# TopPrinter-F0_2_1_PCB.net
KiCad netlist of a schematic drawn in Altium Designer
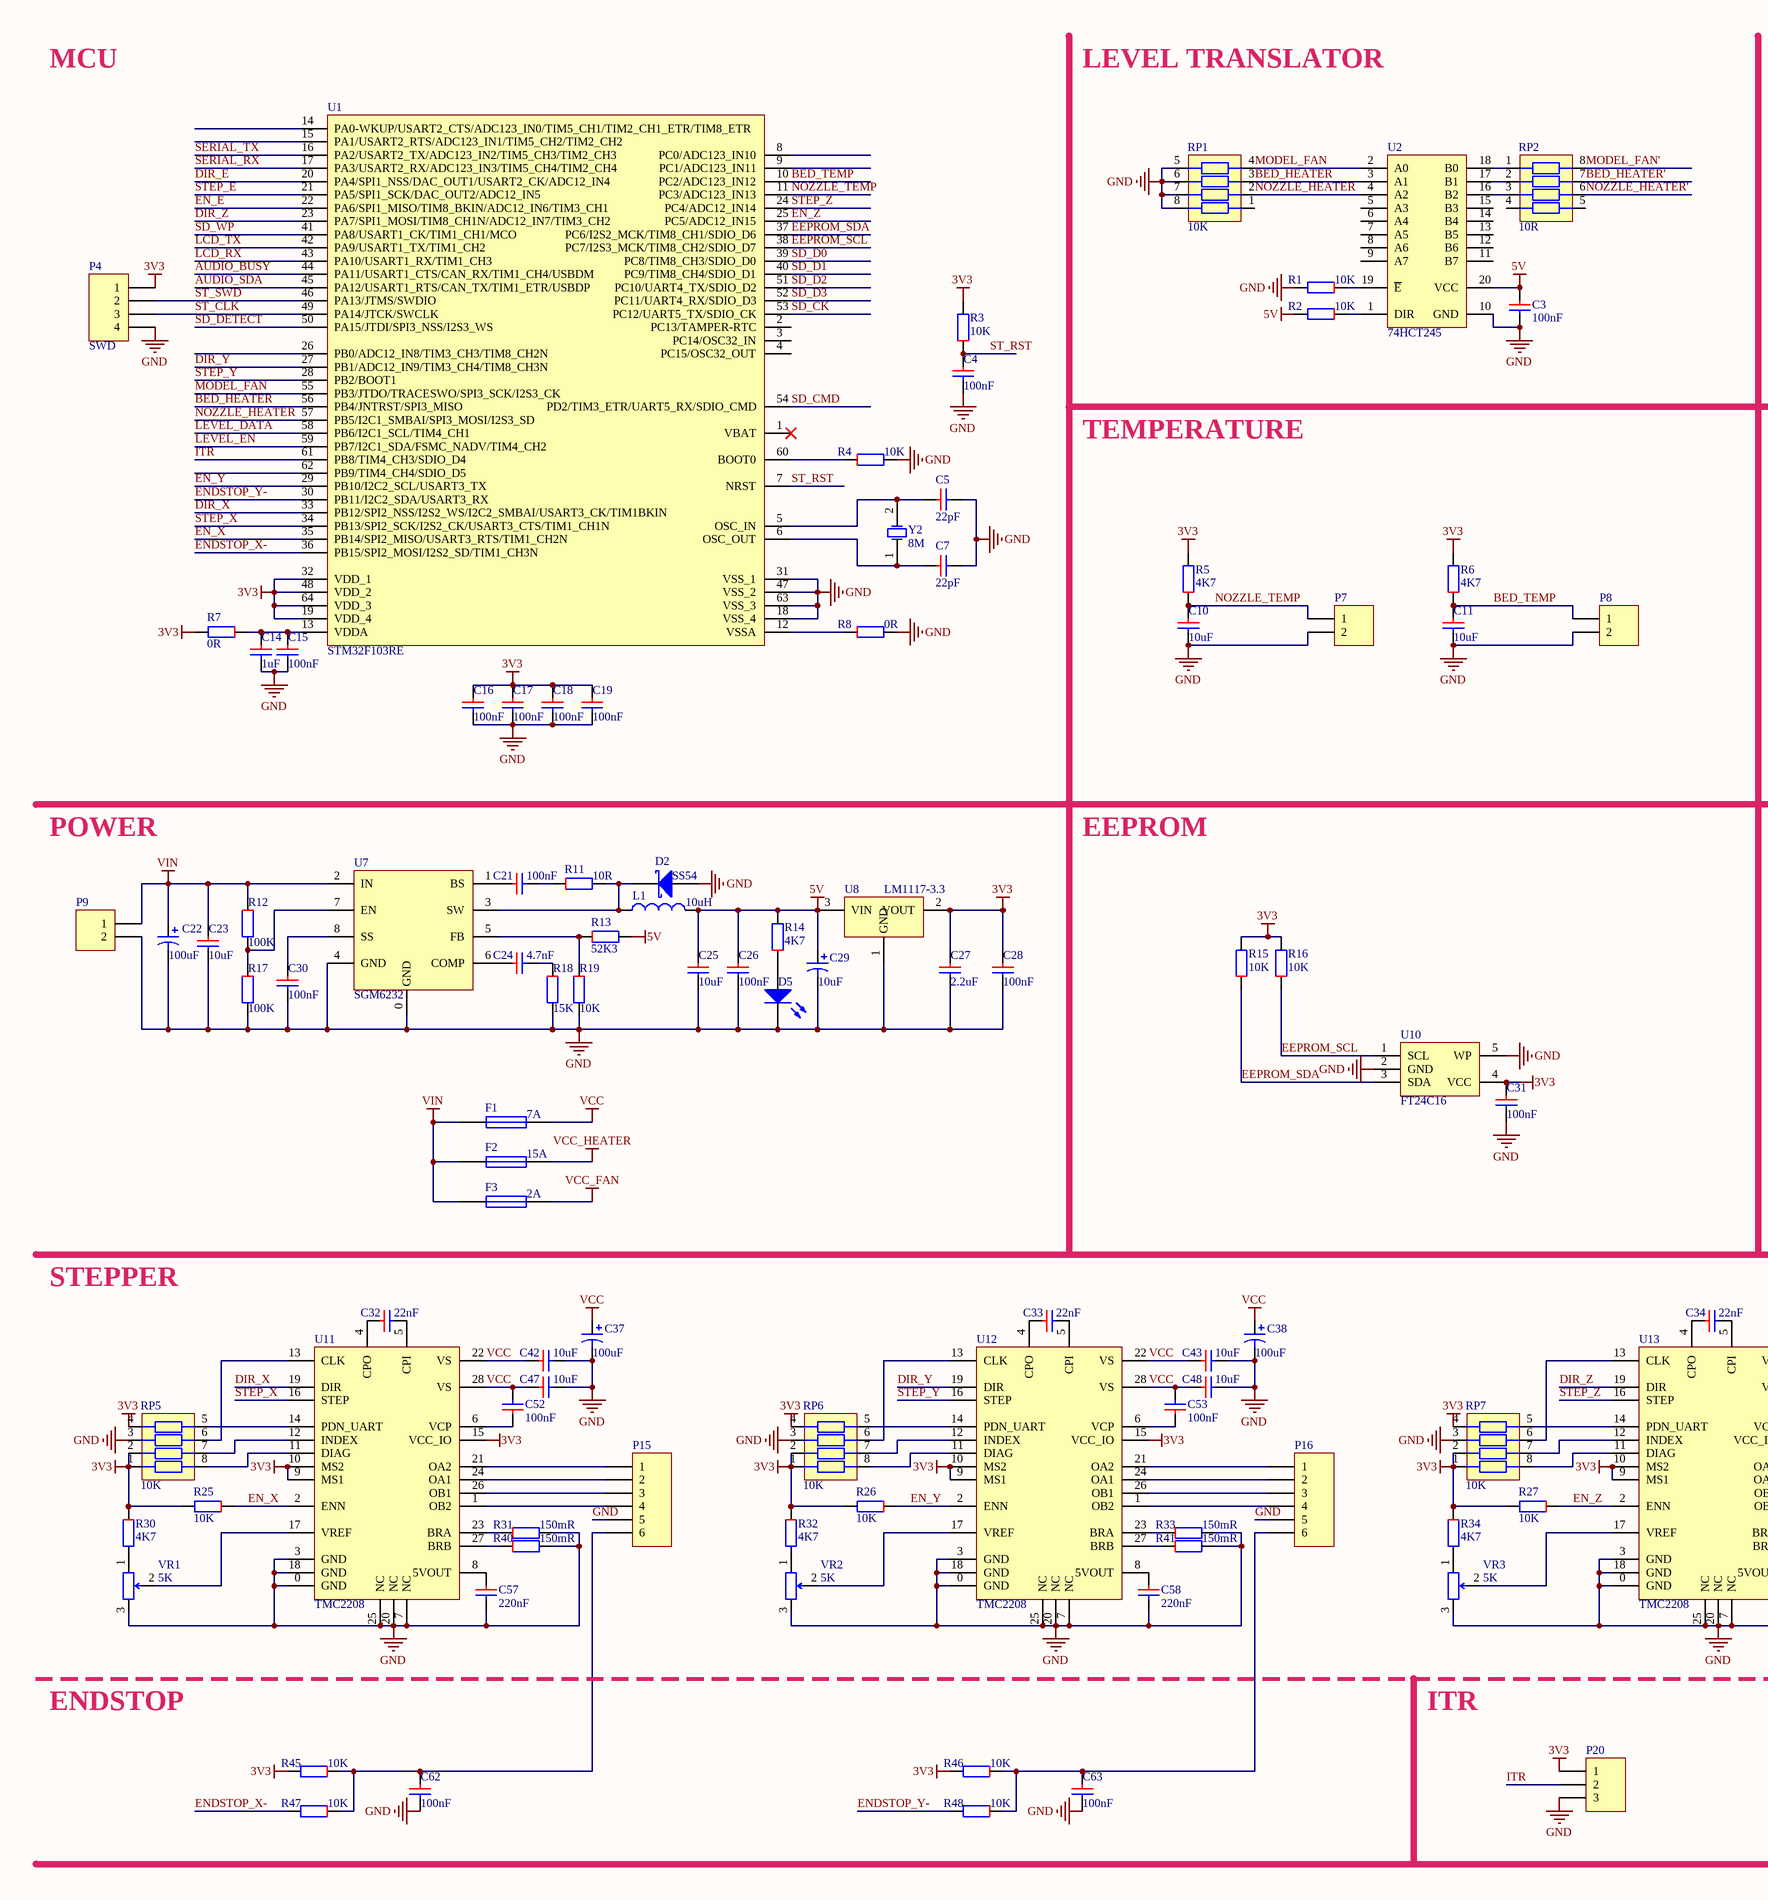
[diagram p0: TopPrinter-F0.2.1_PCB.SchDoc, left]
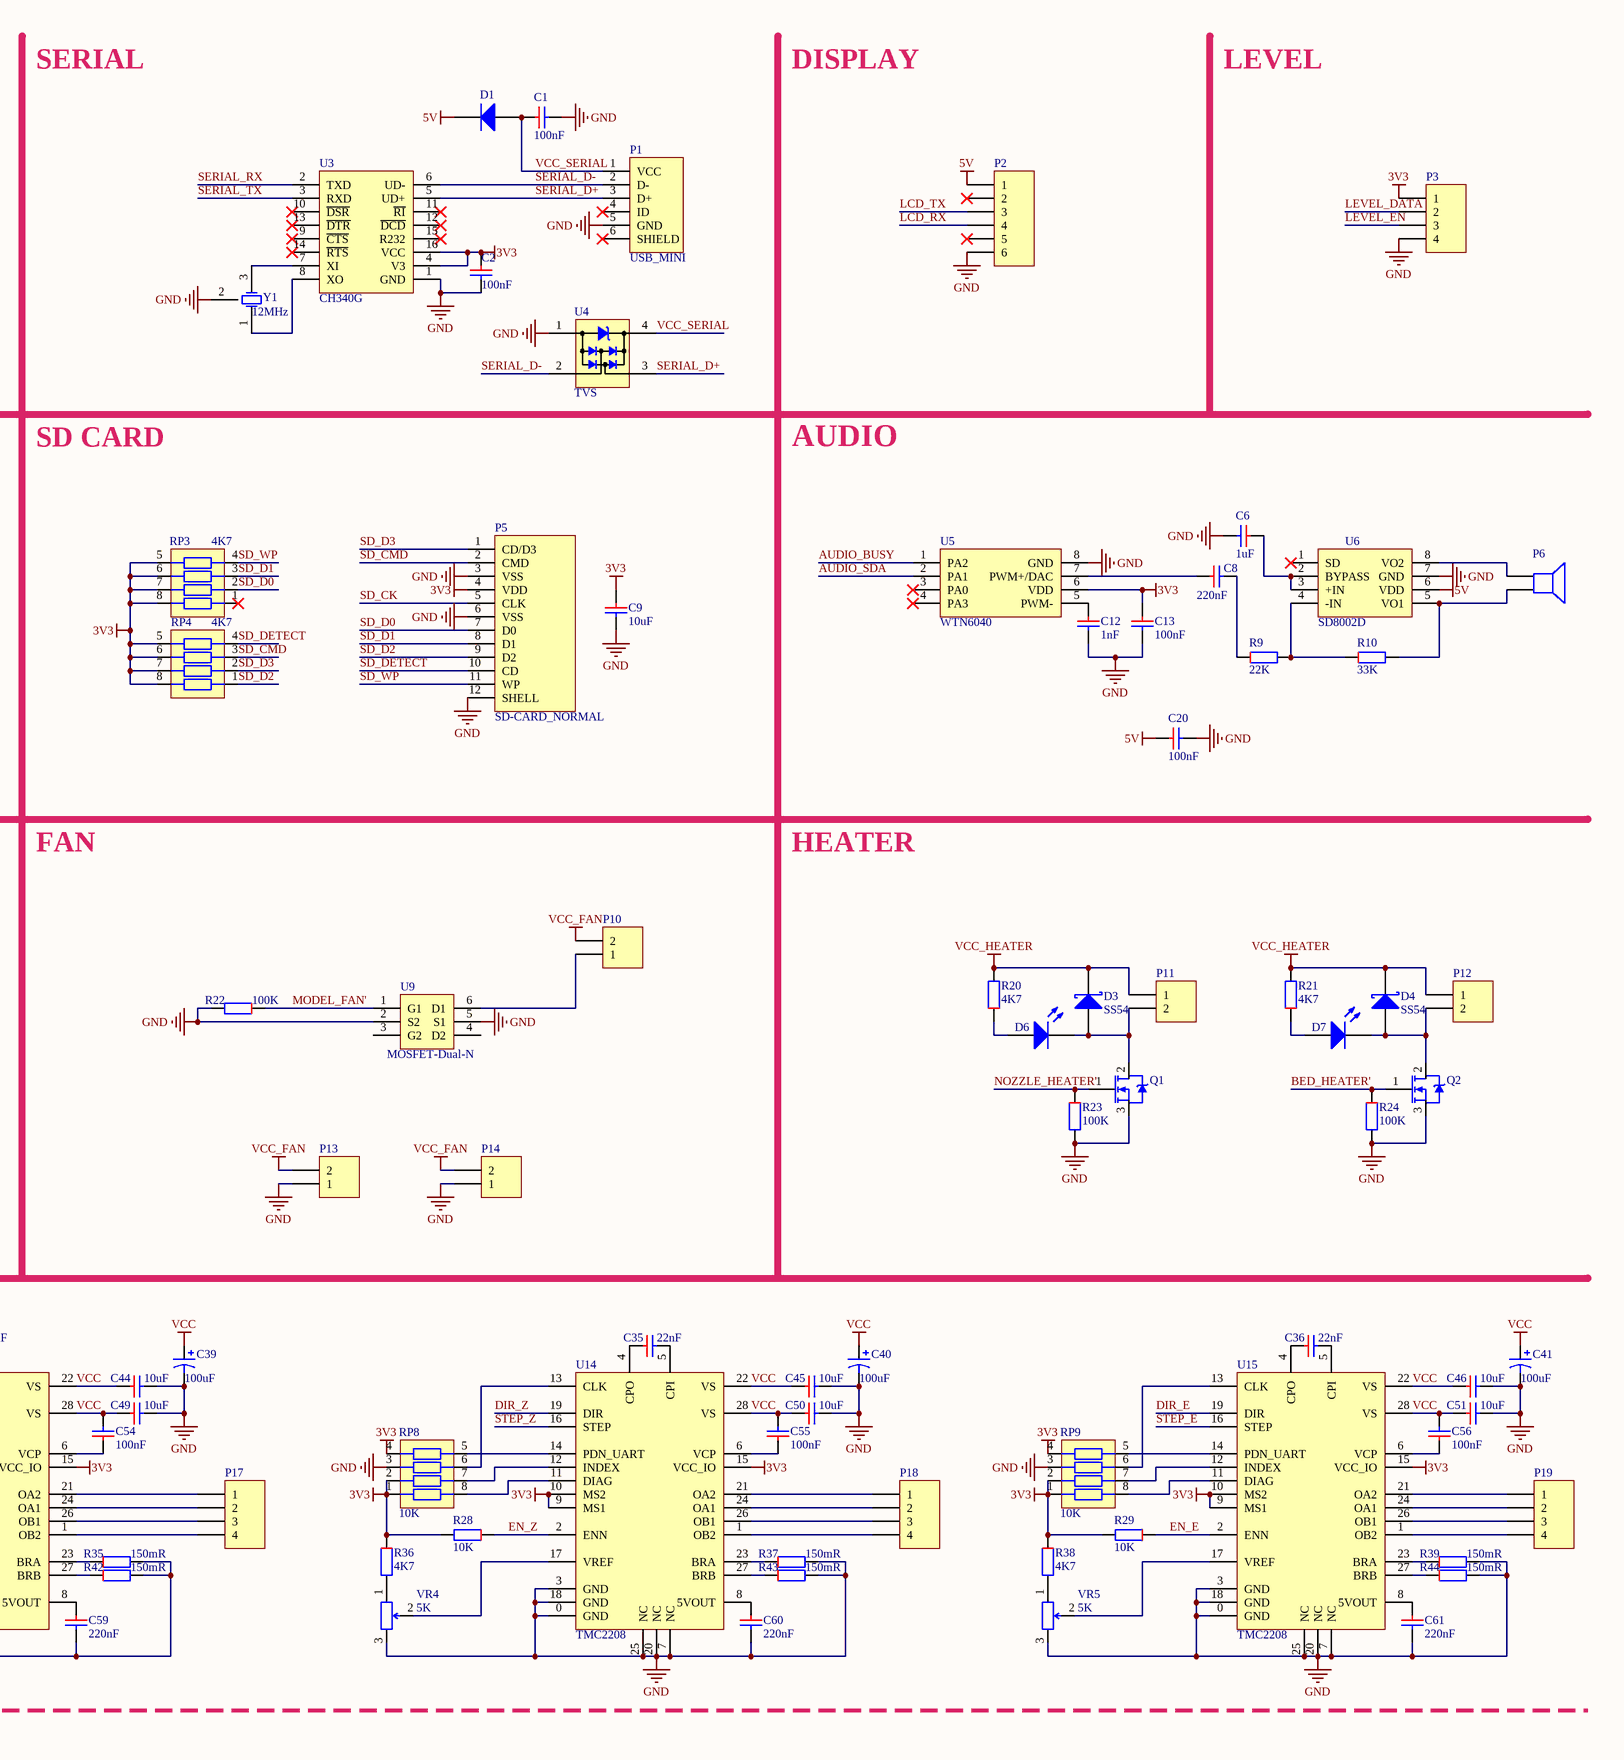
[diagram p1: TopPrinter-F0.2.1_PCB.SchDoc, right]

(export (version "E")
  (design (tool "Eeschema 10.0.6"))
  (components
    (comp (ref "C1")
      (value "100nF")
      (footprint "C-0603")
      (fields (field (name "PUBLISHER") "Altium Limited"))
      (libsource (lib "Printer") (part "Cap"))
    )
    (comp (ref "C2")
      (value "100nF")
      (footprint "C-0603")
      (fields (field (name "PUBLISHER") "Altium Limited"))
      (libsource (lib "Printer") (part "Cap"))
    )
    (comp (ref "C3")
      (value "100nF")
      (footprint "C-0603")
      (fields (field (name "PUBLISHER") "Altium Limited"))
      (libsource (lib "Printer") (part "Cap"))
    )
    (comp (ref "C4")
      (value "100nF")
      (footprint "C-0603")
      (fields (field (name "PUBLISHER") "Altium Limited"))
      (libsource (lib "Printer") (part "Cap"))
    )
    (comp (ref "C5")
      (value "22pF")
      (footprint "C-0603")
      (fields (field (name "PUBLISHER") "Altium Limited"))
      (libsource (lib "Printer") (part "Cap"))
    )
    (comp (ref "C6")
      (value "1uF")
      (footprint "C-0603")
      (fields (field (name "PUBLISHER") "Altium Limited"))
      (libsource (lib "Printer") (part "Cap"))
    )
    (comp (ref "C7")
      (value "22pF")
      (footprint "C-0603")
      (fields (field (name "PUBLISHER") "Altium Limited"))
      (libsource (lib "Printer") (part "Cap"))
    )
    (comp (ref "C8")
      (value "220nF")
      (footprint "C-0603")
      (fields (field (name "PUBLISHER") "Altium Limited"))
      (libsource (lib "Printer") (part "Cap"))
    )
    (comp (ref "C9")
      (value "10uF")
      (footprint "C-0603")
      (fields (field (name "PUBLISHER") "Altium Limited"))
      (libsource (lib "Printer") (part "Cap"))
    )
    (comp (ref "C10")
      (value "10uF")
      (footprint "C-0603")
      (fields (field (name "PUBLISHER") "Altium Limited"))
      (libsource (lib "Printer") (part "Cap"))
    )
    (comp (ref "C11")
      (value "10uF")
      (footprint "C-0603")
      (fields (field (name "PUBLISHER") "Altium Limited"))
      (libsource (lib "Printer") (part "Cap"))
    )
    (comp (ref "C12")
      (value "1nF")
      (footprint "C-0603")
      (fields (field (name "PUBLISHER") "Altium Limited"))
      (libsource (lib "Printer") (part "Cap"))
    )
    (comp (ref "C13")
      (value "100nF")
      (footprint "C-0603")
      (fields (field (name "PUBLISHER") "Altium Limited"))
      (libsource (lib "Printer") (part "Cap"))
    )
    (comp (ref "C14")
      (value "1uF")
      (footprint "C-0603")
      (fields (field (name "PUBLISHER") "Altium Limited"))
      (libsource (lib "Printer") (part "Cap"))
    )
    (comp (ref "C15")
      (value "100nF")
      (footprint "C-0603")
      (fields (field (name "PUBLISHER") "Altium Limited"))
      (libsource (lib "Printer") (part "Cap"))
    )
    (comp (ref "C16")
      (value "100nF")
      (footprint "C-0603")
      (fields (field (name "PUBLISHER") "Altium Limited"))
      (libsource (lib "Printer") (part "Cap"))
    )
    (comp (ref "C17")
      (value "100nF")
      (footprint "C-0603")
      (fields (field (name "PUBLISHER") "Altium Limited"))
      (libsource (lib "Printer") (part "Cap"))
    )
    (comp (ref "C18")
      (value "100nF")
      (footprint "C-0603")
      (fields (field (name "PUBLISHER") "Altium Limited"))
      (libsource (lib "Printer") (part "Cap"))
    )
    (comp (ref "C19")
      (value "100nF")
      (footprint "C-0603")
      (fields (field (name "PUBLISHER") "Altium Limited"))
      (libsource (lib "Printer") (part "Cap"))
    )
    (comp (ref "C20")
      (value "100nF")
      (footprint "C-0603")
      (fields (field (name "PUBLISHER") "Altium Limited"))
      (libsource (lib "Printer") (part "Cap"))
    )
    (comp (ref "C21")
      (value "100nF")
      (footprint "C-0603")
      (fields (field (name "PUBLISHER") "Altium Limited"))
      (libsource (lib "Printer") (part "Cap"))
    )
    (comp (ref "C22")
      (value "100uF")
      (footprint "CAP-6.3x7.7")
      (description "Polarized Capacitor (Radial)")
      (fields (field (name "PUBLISHER") "Altium Limited"))
      (libsource (lib "Miscellaneous Devices") (part "Cap Pol1"))
    )
    (comp (ref "C23")
      (value "10uF")
      (footprint "C-0805")
      (fields (field (name "PUBLISHER") "Altium Limited"))
      (libsource (lib "Printer") (part "Cap"))
    )
    (comp (ref "C24")
      (value "4.7nF")
      (footprint "C-0603")
      (fields (field (name "PUBLISHER") "Altium Limited"))
      (libsource (lib "Printer") (part "Cap"))
    )
    (comp (ref "C25")
      (value "10uF")
      (footprint "C-0805")
      (fields (field (name "PUBLISHER") "Altium Limited"))
      (libsource (lib "Printer") (part "Cap"))
    )
    (comp (ref "C26")
      (value "100nF")
      (footprint "C-0603")
      (fields (field (name "PUBLISHER") "Altium Limited"))
      (libsource (lib "Printer") (part "Cap"))
    )
    (comp (ref "C27")
      (value "2.2uF")
      (footprint "C-0603")
      (fields (field (name "PUBLISHER") "Altium Limited"))
      (libsource (lib "Printer") (part "Cap"))
    )
    (comp (ref "C28")
      (value "100nF")
      (footprint "C-0603")
      (fields (field (name "PUBLISHER") "Altium Limited"))
      (libsource (lib "Printer") (part "Cap"))
    )
    (comp (ref "C29")
      (value "10uF")
      (footprint "TAN-A")
      (description "Polarized Capacitor (Radial)")
      (fields (field (name "PUBLISHER") "Altium Limited"))
      (libsource (lib "Miscellaneous Devices") (part "Cap Pol1"))
    )
    (comp (ref "C30")
      (value "100nF")
      (footprint "C-0603")
      (fields (field (name "PUBLISHER") "Altium Limited"))
      (libsource (lib "Printer") (part "Cap"))
    )
    (comp (ref "C31")
      (value "100nF")
      (footprint "C-0603")
      (fields (field (name "PUBLISHER") "Altium Limited"))
      (libsource (lib "Printer") (part "Cap"))
    )
    (comp (ref "C32")
      (value "22nF")
      (footprint "C-0603")
      (fields (field (name "PUBLISHER") "Altium Limited"))
      (libsource (lib "Printer") (part "Cap"))
    )
    (comp (ref "C33")
      (value "22nF")
      (footprint "C-0603")
      (fields (field (name "PUBLISHER") "Altium Limited"))
      (libsource (lib "Printer") (part "Cap"))
    )
    (comp (ref "C34")
      (value "22nF")
      (footprint "C-0603")
      (fields (field (name "PUBLISHER") "Altium Limited"))
      (libsource (lib "Printer") (part "Cap"))
    )
    (comp (ref "C35")
      (value "22nF")
      (footprint "C-0603")
      (fields (field (name "PUBLISHER") "Altium Limited"))
      (libsource (lib "Printer") (part "Cap"))
    )
    (comp (ref "C36")
      (value "22nF")
      (footprint "C-0603")
      (fields (field (name "PUBLISHER") "Altium Limited"))
      (libsource (lib "Printer") (part "Cap"))
    )
    (comp (ref "C37")
      (value "100uF")
      (footprint "CAP-6.3x7.7")
      (description "Polarized Capacitor (Radial)")
      (fields (field (name "PUBLISHER") "Altium Limited"))
      (libsource (lib "Miscellaneous Devices") (part "Cap Pol1"))
    )
    (comp (ref "C38")
      (value "100uF")
      (footprint "CAP-6.3x7.7")
      (description "Polarized Capacitor (Radial)")
      (fields (field (name "PUBLISHER") "Altium Limited"))
      (libsource (lib "Miscellaneous Devices") (part "Cap Pol1"))
    )
    (comp (ref "C39")
      (value "100uF")
      (footprint "CAP-6.3x7.7")
      (description "Polarized Capacitor (Radial)")
      (fields (field (name "PUBLISHER") "Altium Limited"))
      (libsource (lib "Miscellaneous Devices") (part "Cap Pol1"))
    )
    (comp (ref "C40")
      (value "100uF")
      (footprint "CAP-6.3x7.7")
      (description "Polarized Capacitor (Radial)")
      (fields (field (name "PUBLISHER") "Altium Limited"))
      (libsource (lib "Miscellaneous Devices") (part "Cap Pol1"))
    )
    (comp (ref "C41")
      (value "100uF")
      (footprint "CAP-6.3x7.7")
      (description "Polarized Capacitor (Radial)")
      (fields (field (name "PUBLISHER") "Altium Limited"))
      (libsource (lib "Miscellaneous Devices") (part "Cap Pol1"))
    )
    (comp (ref "C42")
      (value "10uF")
      (footprint "C-0805")
      (fields (field (name "PUBLISHER") "Altium Limited"))
      (libsource (lib "Printer") (part "Cap"))
    )
    (comp (ref "C43")
      (value "10uF")
      (footprint "C-0805")
      (fields (field (name "PUBLISHER") "Altium Limited"))
      (libsource (lib "Printer") (part "Cap"))
    )
    (comp (ref "C44")
      (value "10uF")
      (footprint "C-0805")
      (fields (field (name "PUBLISHER") "Altium Limited"))
      (libsource (lib "Printer") (part "Cap"))
    )
    (comp (ref "C45")
      (value "10uF")
      (footprint "C-0805")
      (fields (field (name "PUBLISHER") "Altium Limited"))
      (libsource (lib "Printer") (part "Cap"))
    )
    (comp (ref "C46")
      (value "10uF")
      (footprint "C-0805")
      (fields (field (name "PUBLISHER") "Altium Limited"))
      (libsource (lib "Printer") (part "Cap"))
    )
    (comp (ref "C47")
      (value "10uF")
      (footprint "C-0805")
      (fields (field (name "PUBLISHER") "Altium Limited"))
      (libsource (lib "Printer") (part "Cap"))
    )
    (comp (ref "C48")
      (value "10uF")
      (footprint "C-0805")
      (fields (field (name "PUBLISHER") "Altium Limited"))
      (libsource (lib "Printer") (part "Cap"))
    )
    (comp (ref "C49")
      (value "10uF")
      (footprint "C-0805")
      (fields (field (name "PUBLISHER") "Altium Limited"))
      (libsource (lib "Printer") (part "Cap"))
    )
    (comp (ref "C50")
      (value "10uF")
      (footprint "C-0805")
      (fields (field (name "PUBLISHER") "Altium Limited"))
      (libsource (lib "Printer") (part "Cap"))
    )
    (comp (ref "C51")
      (value "10uF")
      (footprint "C-0805")
      (fields (field (name "PUBLISHER") "Altium Limited"))
      (libsource (lib "Printer") (part "Cap"))
    )
    (comp (ref "C52")
      (value "100nF")
      (footprint "C-0603")
      (fields (field (name "PUBLISHER") "Altium Limited"))
      (libsource (lib "Printer") (part "Cap"))
    )
    (comp (ref "C53")
      (value "100nF")
      (footprint "C-0603")
      (fields (field (name "PUBLISHER") "Altium Limited"))
      (libsource (lib "Printer") (part "Cap"))
    )
    (comp (ref "C54")
      (value "100nF")
      (footprint "C-0603")
      (fields (field (name "PUBLISHER") "Altium Limited"))
      (libsource (lib "Printer") (part "Cap"))
    )
    (comp (ref "C55")
      (value "100nF")
      (footprint "C-0603")
      (fields (field (name "PUBLISHER") "Altium Limited"))
      (libsource (lib "Printer") (part "Cap"))
    )
    (comp (ref "C56")
      (value "100nF")
      (footprint "C-0603")
      (fields (field (name "PUBLISHER") "Altium Limited"))
      (libsource (lib "Printer") (part "Cap"))
    )
    (comp (ref "C57")
      (value "220nF")
      (footprint "C-0603")
      (fields (field (name "PUBLISHER") "Altium Limited"))
      (libsource (lib "Printer") (part "Cap"))
    )
    (comp (ref "C58")
      (value "220nF")
      (footprint "C-0603")
      (fields (field (name "PUBLISHER") "Altium Limited"))
      (libsource (lib "Printer") (part "Cap"))
    )
    (comp (ref "C59")
      (value "220nF")
      (footprint "C-0603")
      (fields (field (name "PUBLISHER") "Altium Limited"))
      (libsource (lib "Printer") (part "Cap"))
    )
    (comp (ref "C60")
      (value "220nF")
      (footprint "C-0603")
      (fields (field (name "PUBLISHER") "Altium Limited"))
      (libsource (lib "Printer") (part "Cap"))
    )
    (comp (ref "C61")
      (value "220nF")
      (footprint "C-0603")
      (fields (field (name "PUBLISHER") "Altium Limited"))
      (libsource (lib "Printer") (part "Cap"))
    )
    (comp (ref "C62")
      (value "100nF")
      (footprint "C-0603")
      (fields (field (name "PUBLISHER") "Altium Limited"))
      (libsource (lib "Printer") (part "Cap"))
    )
    (comp (ref "C63")
      (value "100nF")
      (footprint "C-0603")
      (fields (field (name "PUBLISHER") "Altium Limited"))
      (libsource (lib "Printer") (part "Cap"))
    )
    (comp (ref "D1")
      (value "MBR0520")
      (footprint "SOD-123")
      (description "Default Diode")
      (fields (field (name "PUBLISHER") "Altium Limited"))
      (libsource (lib "Miscellaneous Devices") (part "Diode"))
    )
    (comp (ref "D2")
      (value "SS54")
      (footprint "DO-214AC")
      (description "Schottky Diode")
      (fields (field (name "PUBLISHER") "Altium Limited"))
      (libsource (lib "Miscellaneous Devices") (part "D Schottky"))
    )
    (comp (ref "D3")
      (value "SS54")
      (footprint "DO-214AC")
      (description "Schottky Diode")
      (fields (field (name "PUBLISHER") "Altium Limited"))
      (libsource (lib "Miscellaneous Devices") (part "D Schottky"))
    )
    (comp (ref "D4")
      (value "SS54")
      (footprint "DO-214AC")
      (description "Schottky Diode")
      (fields (field (name "PUBLISHER") "Altium Limited"))
      (libsource (lib "Miscellaneous Devices") (part "D Schottky"))
    )
    (comp (ref "D5")
      (value "GRE")
      (footprint "LED-0603")
      (description "Typical INFRARED GaAs LED")
      (fields (field (name "PUBLISHER") "Altium Limited"))
      (libsource (lib "Miscellaneous Devices") (part "LED0"))
    )
    (comp (ref "D6")
      (value "BLU")
      (footprint "LED-0603")
      (description "Typical INFRARED GaAs LED")
      (fields (field (name "PUBLISHER") "Altium Limited"))
      (libsource (lib "Miscellaneous Devices") (part "LED0"))
    )
    (comp (ref "D7")
      (value "BLU")
      (footprint "LED-0603")
      (description "Typical INFRARED GaAs LED")
      (fields (field (name "PUBLISHER") "Altium Limited"))
      (libsource (lib "Miscellaneous Devices") (part "LED0"))
    )
    (comp (ref "F1")
      (value "7A")
      (footprint "F-1206")
      (description "Fuse")
      (fields (field (name "PUBLISHER") "Altium Limited"))
      (libsource (lib "Miscellaneous Devices") (part "Fuse 1"))
    )
    (comp (ref "F2")
      (value "15A")
      (footprint "F-1206")
      (description "Fuse")
      (fields (field (name "PUBLISHER") "Altium Limited"))
      (libsource (lib "Miscellaneous Devices") (part "Fuse 1"))
    )
    (comp (ref "F3")
      (value "2A")
      (footprint "F-1206")
      (description "Fuse")
      (fields (field (name "PUBLISHER") "Altium Limited"))
      (libsource (lib "Miscellaneous Devices") (part "Fuse 1"))
    )
    (comp (ref "L1")
      (value "10uH")
      (footprint "L-6045")
      (description "Inductor")
      (fields (field (name "PUBLISHER") "Altium Limited"))
      (libsource (lib "Miscellaneous Devices") (part "Inductor"))
    )
    (comp (ref "P1")
      (value "USB_MINI")
      (footprint "USB-MINI-5P-SMD")
      (libsource (lib "Printer") (part "USB_MINI"))
    )
    (comp (ref "P2")
      (value "~")
      (footprint "XH-6A")
      (description "Header, 6-Pin")
      (fields (field (name "PUBLISHER") "Altium Limited"))
      (libsource (lib "Miscellaneous Connectors") (part "Header 6"))
    )
    (comp (ref "P3")
      (value "~")
      (footprint "XH-4A")
      (description "Header, 4-Pin")
      (fields (field (name "PUBLISHER") "Altium Limited"))
      (libsource (lib "Miscellaneous Connectors") (part "Header 4"))
    )
    (comp (ref "P4")
      (value "SWD")
      (footprint "HDR1X4")
      (description "Header, 4-Pin")
      (fields (field (name "PUBLISHER") "Altium Limited"))
      (libsource (lib "") (part "Header 4_1"))
    )
    (comp (ref "P5")
      (value "SD-CARD_NORMAL")
      (footprint "SD-NORMAL-9P-PUSH")
      (libsource (lib "TopPrinter-T0.2.0") (part "SD-CARD_NORMAL"))
    )
    (comp (ref "P6")
      (value "~")
      (footprint "XH-2A")
      (description "Loudspeaker")
      (fields (field (name "PUBLISHER") "Altium Limited"))
      (libsource (lib "Miscellaneous Devices") (part "Speaker"))
    )
    (comp (ref "P7")
      (value "~")
      (footprint "XH-2A")
      (description "Header, 2-Pin")
      (fields (field (name "PUBLISHER") "Altium Limited"))
      (libsource (lib "") (part "Header 2_1"))
    )
    (comp (ref "P8")
      (value "~")
      (footprint "XH-2A")
      (description "Header, 2-Pin")
      (fields (field (name "PUBLISHER") "Altium Limited"))
      (libsource (lib "") (part "Header 2_1"))
    )
    (comp (ref "P9")
      (value "~")
      (footprint "CON-5.0-2P")
      (description "Header, 2-Pin")
      (fields (field (name "PUBLISHER") "Altium Limited"))
      (libsource (lib "") (part "Header 2_2"))
    )
    (comp (ref "P10")
      (value "~")
      (footprint "XH-2A")
      (description "Header, 2-Pin")
      (fields (field (name "PUBLISHER") "Altium Limited"))
      (libsource (lib "Miscellaneous Connectors") (part "Header 2"))
    )
    (comp (ref "P11")
      (value "~")
      (footprint "CON-5.0-2P")
      (description "Header, 2-Pin")
      (fields (field (name "PUBLISHER") "Altium Limited"))
      (libsource (lib "") (part "Header 2_1"))
    )
    (comp (ref "P12")
      (value "~")
      (footprint "CON-5.0-2P")
      (description "Header, 2-Pin")
      (fields (field (name "PUBLISHER") "Altium Limited"))
      (libsource (lib "") (part "Header 2_1"))
    )
    (comp (ref "P13")
      (value "~")
      (footprint "XH-2A")
      (description "Header, 2-Pin")
      (fields (field (name "PUBLISHER") "Altium Limited"))
      (libsource (lib "Miscellaneous Connectors") (part "Header 2"))
    )
    (comp (ref "P14")
      (value "~")
      (footprint "XH-2A")
      (description "Header, 2-Pin")
      (fields (field (name "PUBLISHER") "Altium Limited"))
      (libsource (lib "Miscellaneous Connectors") (part "Header 2"))
    )
    (comp (ref "P15")
      (value "~")
      (footprint "XH-6A")
      (description "Header, 6-Pin")
      (fields (field (name "PUBLISHER") "Altium Limited"))
      (libsource (lib "Miscellaneous Connectors") (part "Header 6"))
    )
    (comp (ref "P16")
      (value "~")
      (footprint "XH-6A")
      (description "Header, 6-Pin")
      (fields (field (name "PUBLISHER") "Altium Limited"))
      (libsource (lib "Miscellaneous Connectors") (part "Header 6"))
    )
    (comp (ref "P17")
      (value "~")
      (footprint "XH-4A")
      (description "Header, 4-Pin")
      (fields (field (name "PUBLISHER") "Altium Limited"))
      (libsource (lib "Miscellaneous Connectors") (part "Header 4"))
    )
    (comp (ref "P18")
      (value "~")
      (footprint "XH-4A")
      (description "Header, 4-Pin")
      (fields (field (name "PUBLISHER") "Altium Limited"))
      (libsource (lib "Miscellaneous Connectors") (part "Header 4"))
    )
    (comp (ref "P19")
      (value "~")
      (footprint "XH-4A")
      (description "Header, 4-Pin")
      (fields (field (name "PUBLISHER") "Altium Limited"))
      (libsource (lib "Miscellaneous Connectors") (part "Header 4"))
    )
    (comp (ref "P20")
      (value "Header 3")
      (footprint "XH-3A")
      (description "Header, 3-Pin")
      (fields (field (name "PUBLISHER") "Altium Limited"))
      (libsource (lib "Miscellaneous Connectors") (part "Header 3"))
    )
    (comp (ref "Q1")
      (value "HY3403D")
      (footprint "TO-252-2")
      (libsource (lib "Creality3D_H750IB") (part "MOSFET-N"))
    )
    (comp (ref "Q2")
      (value "HY3403D")
      (footprint "TO-252-2")
      (libsource (lib "Creality3D_H750IB") (part "MOSFET-N"))
    )
    (comp (ref "R1")
      (value "10K")
      (footprint "R-0603")
      (fields (field (name "PUBLISHER") "Altium Limited"))
      (libsource (lib "Printer") (part "Res"))
    )
    (comp (ref "R2")
      (value "10K")
      (footprint "R-0603")
      (fields (field (name "PUBLISHER") "Altium Limited"))
      (libsource (lib "Printer") (part "Res"))
    )
    (comp (ref "R3")
      (value "10K")
      (footprint "R-0603")
      (fields (field (name "PUBLISHER") "Altium Limited"))
      (libsource (lib "Printer") (part "Res"))
    )
    (comp (ref "R4")
      (value "10K")
      (footprint "R-0603")
      (fields (field (name "PUBLISHER") "Altium Limited"))
      (libsource (lib "Printer") (part "Res"))
    )
    (comp (ref "R5")
      (value "4K7")
      (footprint "R-0603")
      (fields (field (name "PUBLISHER") "Altium Limited"))
      (libsource (lib "Printer") (part "Res"))
    )
    (comp (ref "R6")
      (value "4K7")
      (footprint "R-0603")
      (fields (field (name "PUBLISHER") "Altium Limited"))
      (libsource (lib "Printer") (part "Res"))
    )
    (comp (ref "R7")
      (value "0R")
      (footprint "R-0603")
      (fields (field (name "PUBLISHER") "Altium Limited"))
      (libsource (lib "Printer") (part "Res"))
    )
    (comp (ref "R8")
      (value "0R")
      (footprint "R-0603")
      (fields (field (name "PUBLISHER") "Altium Limited"))
      (libsource (lib "Printer") (part "Res"))
    )
    (comp (ref "R9")
      (value "22K")
      (footprint "R-0603")
      (fields (field (name "PUBLISHER") "Altium Limited"))
      (libsource (lib "Printer") (part "Res"))
    )
    (comp (ref "R10")
      (value "33K")
      (footprint "R-0603")
      (fields (field (name "PUBLISHER") "Altium Limited"))
      (libsource (lib "Printer") (part "Res"))
    )
    (comp (ref "R11")
      (value "10R")
      (footprint "R-0603")
      (fields (field (name "PUBLISHER") "Altium Limited"))
      (libsource (lib "Printer") (part "Res"))
    )
    (comp (ref "R12")
      (value "100K")
      (footprint "R-0603")
      (fields (field (name "PUBLISHER") "Altium Limited"))
      (libsource (lib "Printer") (part "Res"))
    )
    (comp (ref "R13")
      (value "52K3")
      (footprint "R-0603")
      (fields (field (name "PUBLISHER") "Altium Limited"))
      (libsource (lib "Printer") (part "Res"))
    )
    (comp (ref "R14")
      (value "4K7")
      (footprint "R-0603")
      (fields (field (name "PUBLISHER") "Altium Limited"))
      (libsource (lib "Printer") (part "Res"))
    )
    (comp (ref "R15")
      (value "10K")
      (footprint "R-0603")
      (fields (field (name "PUBLISHER") "Altium Limited"))
      (libsource (lib "Printer") (part "Res"))
    )
    (comp (ref "R16")
      (value "10K")
      (footprint "R-0603")
      (fields (field (name "PUBLISHER") "Altium Limited"))
      (libsource (lib "Printer") (part "Res"))
    )
    (comp (ref "R17")
      (value "100K")
      (footprint "R-0603")
      (fields (field (name "PUBLISHER") "Altium Limited"))
      (libsource (lib "Printer") (part "Res"))
    )
    (comp (ref "R18")
      (value "15K")
      (footprint "R-0603")
      (fields (field (name "PUBLISHER") "Altium Limited"))
      (libsource (lib "Printer") (part "Res"))
    )
    (comp (ref "R19")
      (value "10K")
      (footprint "R-0603")
      (fields (field (name "PUBLISHER") "Altium Limited"))
      (libsource (lib "Printer") (part "Res"))
    )
    (comp (ref "R20")
      (value "4K7")
      (footprint "R-0603")
      (fields (field (name "PUBLISHER") "Altium Limited"))
      (libsource (lib "Printer") (part "Res"))
    )
    (comp (ref "R21")
      (value "4K7")
      (footprint "R-0603")
      (fields (field (name "PUBLISHER") "Altium Limited"))
      (libsource (lib "Printer") (part "Res"))
    )
    (comp (ref "R22")
      (value "100K")
      (footprint "R-0603")
      (fields (field (name "PUBLISHER") "Altium Limited"))
      (libsource (lib "Printer") (part "Res"))
    )
    (comp (ref "R23")
      (value "100K")
      (footprint "R-0603")
      (fields (field (name "PUBLISHER") "Altium Limited"))
      (libsource (lib "Printer") (part "Res"))
    )
    (comp (ref "R24")
      (value "100K")
      (footprint "R-0603")
      (fields (field (name "PUBLISHER") "Altium Limited"))
      (libsource (lib "Printer") (part "Res"))
    )
    (comp (ref "R25")
      (value "10K")
      (footprint "R-0603")
      (fields (field (name "PUBLISHER") "Altium Limited"))
      (libsource (lib "Printer") (part "Res"))
    )
    (comp (ref "R26")
      (value "10K")
      (footprint "R-0603")
      (fields (field (name "PUBLISHER") "Altium Limited"))
      (libsource (lib "Printer") (part "Res"))
    )
    (comp (ref "R27")
      (value "10K")
      (footprint "R-0603")
      (fields (field (name "PUBLISHER") "Altium Limited"))
      (libsource (lib "Printer") (part "Res"))
    )
    (comp (ref "R28")
      (value "10K")
      (footprint "R-0603")
      (fields (field (name "PUBLISHER") "Altium Limited"))
      (libsource (lib "Printer") (part "Res"))
    )
    (comp (ref "R29")
      (value "10K")
      (footprint "R-0603")
      (fields (field (name "PUBLISHER") "Altium Limited"))
      (libsource (lib "Printer") (part "Res"))
    )
    (comp (ref "R30")
      (value "4K7")
      (footprint "R-0603")
      (fields (field (name "PUBLISHER") "Altium Limited"))
      (libsource (lib "Printer") (part "Res"))
    )
    (comp (ref "R31")
      (value "150mR")
      (footprint "R-1206")
      (fields (field (name "PUBLISHER") "Altium Limited"))
      (libsource (lib "Printer") (part "Res"))
    )
    (comp (ref "R32")
      (value "4K7")
      (footprint "R-0603")
      (fields (field (name "PUBLISHER") "Altium Limited"))
      (libsource (lib "Printer") (part "Res"))
    )
    (comp (ref "R33")
      (value "150mR")
      (footprint "R-1206")
      (fields (field (name "PUBLISHER") "Altium Limited"))
      (libsource (lib "Printer") (part "Res"))
    )
    (comp (ref "R34")
      (value "4K7")
      (footprint "R-0603")
      (fields (field (name "PUBLISHER") "Altium Limited"))
      (libsource (lib "Printer") (part "Res"))
    )
    (comp (ref "R35")
      (value "150mR")
      (footprint "R-1206")
      (fields (field (name "PUBLISHER") "Altium Limited"))
      (libsource (lib "Printer") (part "Res"))
    )
    (comp (ref "R36")
      (value "4K7")
      (footprint "R-0603")
      (fields (field (name "PUBLISHER") "Altium Limited"))
      (libsource (lib "Printer") (part "Res"))
    )
    (comp (ref "R37")
      (value "150mR")
      (footprint "R-1206")
      (fields (field (name "PUBLISHER") "Altium Limited"))
      (libsource (lib "Printer") (part "Res"))
    )
    (comp (ref "R38")
      (value "4K7")
      (footprint "R-0603")
      (fields (field (name "PUBLISHER") "Altium Limited"))
      (libsource (lib "Printer") (part "Res"))
    )
    (comp (ref "R39")
      (value "150mR")
      (footprint "R-1206")
      (fields (field (name "PUBLISHER") "Altium Limited"))
      (libsource (lib "Printer") (part "Res"))
    )
    (comp (ref "R40")
      (value "150mR")
      (footprint "R-1206")
      (fields (field (name "PUBLISHER") "Altium Limited"))
      (libsource (lib "Printer") (part "Res"))
    )
    (comp (ref "R41")
      (value "150mR")
      (footprint "R-1206")
      (fields (field (name "PUBLISHER") "Altium Limited"))
      (libsource (lib "Printer") (part "Res"))
    )
    (comp (ref "R42")
      (value "150mR")
      (footprint "R-1206")
      (fields (field (name "PUBLISHER") "Altium Limited"))
      (libsource (lib "Printer") (part "Res"))
    )
    (comp (ref "R43")
      (value "150mR")
      (footprint "R-1206")
      (fields (field (name "PUBLISHER") "Altium Limited"))
      (libsource (lib "Printer") (part "Res"))
    )
    (comp (ref "R44")
      (value "150mR")
      (footprint "R-1206")
      (fields (field (name "PUBLISHER") "Altium Limited"))
      (libsource (lib "Printer") (part "Res"))
    )
    (comp (ref "R45")
      (value "10K")
      (footprint "R-0603")
      (fields (field (name "PUBLISHER") "Altium Limited"))
      (libsource (lib "Printer") (part "Res"))
    )
    (comp (ref "R46")
      (value "10K")
      (footprint "R-0603")
      (fields (field (name "PUBLISHER") "Altium Limited"))
      (libsource (lib "Printer") (part "Res"))
    )
    (comp (ref "R47")
      (value "10K")
      (footprint "R-0603")
      (fields (field (name "PUBLISHER") "Altium Limited"))
      (libsource (lib "Printer") (part "Res"))
    )
    (comp (ref "R48")
      (value "10K")
      (footprint "R-0603")
      (fields (field (name "PUBLISHER") "Altium Limited"))
      (libsource (lib "Printer") (part "Res"))
    )
    (comp (ref "RP1")
      (value "10K")
      (footprint "R-0603x4")
      (fields (field (name "PUBLISHER") "Altium Limited"))
      (libsource (lib "RGB_LCD转接板v1") (part "RES-PACK"))
    )
    (comp (ref "RP2")
      (value "10R")
      (footprint "R-0603x4")
      (fields (field (name "PUBLISHER") "Altium Limited"))
      (libsource (lib "") (part "RES-PACK_1"))
    )
    (comp (ref "RP3")
      (value "4K7")
      (footprint "R-0603x4")
      (fields (field (name "PUBLISHER") "Altium Limited"))
      (libsource (lib "RGB_LCD转接板v1") (part "RES-PACK"))
    )
    (comp (ref "RP4")
      (value "4K7")
      (footprint "R-0603x4")
      (fields (field (name "PUBLISHER") "Altium Limited"))
      (libsource (lib "RGB_LCD转接板v1") (part "RES-PACK"))
    )
    (comp (ref "RP5")
      (value "10K")
      (footprint "R-0603x4")
      (fields (field (name "PUBLISHER") "Altium Limited"))
      (libsource (lib "Printer") (part "RES-PACK"))
    )
    (comp (ref "RP6")
      (value "10K")
      (footprint "R-0603x4")
      (fields (field (name "PUBLISHER") "Altium Limited"))
      (libsource (lib "Printer") (part "RES-PACK"))
    )
    (comp (ref "RP7")
      (value "10K")
      (footprint "R-0603x4")
      (fields (field (name "PUBLISHER") "Altium Limited"))
      (libsource (lib "Printer") (part "RES-PACK"))
    )
    (comp (ref "RP8")
      (value "10K")
      (footprint "R-0603x4")
      (fields (field (name "PUBLISHER") "Altium Limited"))
      (libsource (lib "Printer") (part "RES-PACK"))
    )
    (comp (ref "RP9")
      (value "10K")
      (footprint "R-0603x4")
      (fields (field (name "PUBLISHER") "Altium Limited"))
      (libsource (lib "Printer") (part "RES-PACK"))
    )
    (comp (ref "U1")
      (value "STM32F103RE")
      (footprint "LQFP-64")
      (libsource (lib "Printer") (part "STM32F103RC"))
    )
    (comp (ref "U2")
      (value "74HCT245")
      (footprint "TSSOP-20")
      (libsource (lib "Creality3D_H750IB") (part "74HCT245"))
    )
    (comp (ref "U3")
      (value "CH340G")
      (footprint "SOIC-16-150MIL")
      (libsource (lib "Printer") (part "CH340G"))
    )
    (comp (ref "U4") (value "TVS") (footprint "SOT-143") (libsource (lib "Printer") (part "TVS")))
    (comp (ref "U5")
      (value "WTN6040")
      (footprint "SOIC-8-150MIL")
      (libsource (lib "Creality3D_H750IB") (part "WTN6040"))
    )
    (comp (ref "U6")
      (value "SD8002D")
      (footprint "SOIC-8-150MIL")
      (libsource (lib "Creality3D_H750IB_V3.0.4") (part "SD8002D"))
    )
    (comp (ref "U7")
      (value "SGM6232")
      (footprint "SOIC-8-150MIL-PAD")
      (libsource (lib "Printer") (part "SGM6232"))
    )
    (comp (ref "U8")
      (value "LM1117-3.3")
      (footprint "SOT-223")
      (libsource (lib "Creality3D_H750IB") (part "LM1117"))
    )
    (comp (ref "U9")
      (value "MOSFET-Dual-N")
      (footprint "SOT-23-6")
      (libsource (lib "Creality3D_H750IB") (part "MOSFET-Dual-N"))
    )
    (comp (ref "U10") (value "FT24C16") (footprint "SOT-23-5") (libsource (lib "Printer") (part "FT24C16")))
    (comp (ref "U11")
      (value "TMC2208")
      (footprint "QFN-28-5x5x05")
      (libsource (lib "TopPrinter-F0.1.0") (part "TMC2208"))
    )
    (comp (ref "U12")
      (value "TMC2208")
      (footprint "QFN-28-5x5x05")
      (libsource (lib "TopPrinter-F0.1.0") (part "TMC2208"))
    )
    (comp (ref "U13")
      (value "TMC2208")
      (footprint "QFN-28-5x5x05")
      (libsource (lib "TopPrinter-F0.1.0") (part "TMC2208"))
    )
    (comp (ref "U14")
      (value "TMC2208")
      (footprint "QFN-28-5x5x05")
      (libsource (lib "TopPrinter-F0.1.0") (part "TMC2208"))
    )
    (comp (ref "U15")
      (value "TMC2208")
      (footprint "QFN-28-5x5x05")
      (libsource (lib "TopPrinter-F0.1.0") (part "TMC2208"))
    )
    (comp (ref "VR1")
      (value "5K")
      (footprint "RP-3MM-SMD")
      (fields (field (name "PUBLISHER") "Altium Limited"))
      (libsource (lib "Printer") (part "RES-TAP"))
    )
    (comp (ref "VR2")
      (value "5K")
      (footprint "RP-3MM-SMD")
      (fields (field (name "PUBLISHER") "Altium Limited"))
      (libsource (lib "Printer") (part "RES-TAP"))
    )
    (comp (ref "VR3")
      (value "5K")
      (footprint "RP-3MM-SMD")
      (fields (field (name "PUBLISHER") "Altium Limited"))
      (libsource (lib "Printer") (part "RES-TAP"))
    )
    (comp (ref "VR4")
      (value "5K")
      (footprint "RP-3MM-SMD")
      (fields (field (name "PUBLISHER") "Altium Limited"))
      (libsource (lib "Printer") (part "RES-TAP"))
    )
    (comp (ref "VR5")
      (value "5K")
      (footprint "RP-3MM-SMD")
      (fields (field (name "PUBLISHER") "Altium Limited"))
      (libsource (lib "Printer") (part "RES-TAP"))
    )
    (comp (ref "Y1")
      (value "12MHz")
      (footprint "XTAL-3215-3P")
      (description "Crystal Oscillator")
      (fields (field (name "PUBLISHER") "Altium Limited"))
      (libsource (lib "H750元件库") (part "XTAL"))
    )
    (comp (ref "Y2")
      (value "8M")
      (footprint "XTAL-5032-2P")
      (description "Crystal Oscillator")
      (fields (field (name "PUBLISHER") "Altium Limited"))
      (libsource (lib "Miscellaneous Devices") (part "XTAL"))
    )
  )
  (nets
    (net (code "1") (name "/AUDIO_BUSY") (class "Default")
      (node (ref "U1") (pin "44") (pinfunction "PA11/USART1_CTS/CAN_RX/TIM1_CH4/USBDM_44") (pintype "passive"))
      (node (ref "U5") (pin "1") (pinfunction "PA2_1") (pintype "passive"))
    )
    (net (code "2") (name "/AUDIO_SDA") (class "Default")
      (node (ref "U1") (pin "45") (pinfunction "PA12/USART1_RTS/CAN_TX/TIM1_ETR/USBDP_45") (pintype "passive"))
      (node (ref "U5") (pin "2") (pinfunction "PA1_2") (pintype "passive"))
    )
    (net (code "3") (name "/BED_HEATER") (class "Default")
      (node (ref "RP1") (pin "3") (pinfunction "1_3") (pintype "passive"))
      (node (ref "U1") (pin "56") (pinfunction "PB4/JNTRST/SPI3_MISO_56") (pintype "passive"))
      (node (ref "U2") (pin "3") (pinfunction "A1_3") (pintype "passive"))
    )
    (net (code "4") (name "/BED_HEATER'") (class "Default")
      (node (ref "Q2") (pin "1") (pinfunction "G_1") (pintype "passive"))
      (node (ref "R24") (pin "1") (pinfunction "1_1") (pintype "passive"))
      (node (ref "RP2") (pin "7") (pinfunction "1_7") (pintype "passive"))
    )
    (net (code "5") (name "/BED_TEMP") (class "Default")
      (node (ref "C11") (pin "1") (pinfunction "1_1") (pintype "passive"))
      (node (ref "P8") (pin "1") (pinfunction "1_1") (pintype "passive"))
      (node (ref "R6") (pin "1") (pinfunction "1_1") (pintype "passive"))
      (node (ref "U1") (pin "10") (pinfunction "PC2/ADC123_IN12_10") (pintype "passive"))
    )
    (net (code "6") (name "/DIR_E") (class "Default")
      (node (ref "U1") (pin "20") (pinfunction "PA4/SPI1_NSS/DAC_OUT1/USART2_CK/ADC12_IN4_20") (pintype "passive"))
      (node (ref "U15") (pin "19") (pinfunction "DIR_19") (pintype "passive"))
    )
    (net (code "7") (name "/DIR_X") (class "Default")
      (node (ref "U1") (pin "33") (pinfunction "PB12/SPI2_NSS/I2S2_WS/I2C2_SMBAI/USART3_CK/TIM1BKIN_33") (pintype "passive"))
      (node (ref "U11") (pin "19") (pinfunction "DIR_19") (pintype "passive"))
    )
    (net (code "8") (name "/DIR_Y") (class "Default")
      (node (ref "U1") (pin "27") (pinfunction "PB1/ADC12_IN9/TIM3_CH4/TIM8_CH3N_27") (pintype "passive"))
      (node (ref "U12") (pin "19") (pinfunction "DIR_19") (pintype "passive"))
    )
    (net (code "9") (name "/DIR_Z") (class "Default")
      (node (ref "U1") (pin "23") (pinfunction "PA7/SPI1_MOSI/TIM8_CH1N/ADC12_IN7/TIM3_CH2_23") (pintype "passive"))
      (node (ref "U13") (pin "19") (pinfunction "DIR_19") (pintype "passive"))
      (node (ref "U14") (pin "19") (pinfunction "DIR_19") (pintype "passive"))
    )
    (net (code "10") (name "/EEPROM_SCL") (class "Default")
      (node (ref "R16") (pin "1") (pinfunction "1_1") (pintype "passive"))
      (node (ref "U1") (pin "38") (pinfunction "PC7/I2S3_MCK/TIM8_CH2/SDIO_D7_38") (pintype "passive"))
      (node (ref "U10") (pin "1") (pinfunction "SCL_1") (pintype "passive"))
    )
    (net (code "11") (name "/EEPROM_SDA") (class "Default")
      (node (ref "R15") (pin "1") (pinfunction "1_1") (pintype "passive"))
      (node (ref "U1") (pin "37") (pinfunction "PC6/I2S2_MCK/TIM8_CH1/SDIO_D6_37") (pintype "passive"))
      (node (ref "U10") (pin "3") (pinfunction "SDA_3") (pintype "passive"))
    )
    (net (code "12") (name "/ENDSTOP_X-") (class "Default")
      (node (ref "R47") (pin "2") (pinfunction "2_2") (pintype "passive"))
      (node (ref "U1") (pin "36") (pinfunction "PB15/SPI2_MOSI/I2S2_SD/TIM1_CH3N_36") (pintype "passive"))
    )
    (net (code "13") (name "/ENDSTOP_Y-") (class "Default")
      (node (ref "R48") (pin "2") (pinfunction "2_2") (pintype "passive"))
      (node (ref "U1") (pin "30") (pinfunction "PB11/I2C2_SDA/USART3_RX_30") (pintype "passive"))
    )
    (net (code "14") (name "/EN_E") (class "Default")
      (node (ref "R29") (pin "1") (pinfunction "1_1") (pintype "passive"))
      (node (ref "U1") (pin "22") (pinfunction "PA6/SPI1_MISO/TIM8_BKIN/ADC12_IN6/TIM3_CH1_22") (pintype "passive"))
      (node (ref "U15") (pin "2") (pinfunction "ENN_2") (pintype "passive"))
    )
    (net (code "15") (name "/EN_X") (class "Default")
      (node (ref "R25") (pin "1") (pinfunction "1_1") (pintype "passive"))
      (node (ref "U1") (pin "35") (pinfunction "PB14/SPI2_MISO/USART3_RTS/TIM1_CH2N_35") (pintype "passive"))
      (node (ref "U11") (pin "2") (pinfunction "ENN_2") (pintype "passive"))
    )
    (net (code "16") (name "/EN_Y") (class "Default")
      (node (ref "R26") (pin "1") (pinfunction "1_1") (pintype "passive"))
      (node (ref "U1") (pin "29") (pinfunction "PB10/I2C2_SCL/USART3_TX_29") (pintype "passive"))
      (node (ref "U12") (pin "2") (pinfunction "ENN_2") (pintype "passive"))
    )
    (net (code "17") (name "/EN_Z") (class "Default")
      (node (ref "R27") (pin "1") (pinfunction "1_1") (pintype "passive"))
      (node (ref "R28") (pin "1") (pinfunction "1_1") (pintype "passive"))
      (node (ref "U1") (pin "25") (pinfunction "PC5/ADC12_IN15_25") (pintype "passive"))
      (node (ref "U13") (pin "2") (pinfunction "ENN_2") (pintype "passive"))
      (node (ref "U14") (pin "2") (pinfunction "ENN_2") (pintype "passive"))
    )
    (net (code "18") (name "/ITR") (class "Default")
      (node (ref "P20") (pin "2") (pinfunction "2_2") (pintype "passive"))
      (node (ref "U1") (pin "61") (pinfunction "PB8/TIM4_CH3/SDIO_D4_61") (pintype "passive"))
    )
    (net (code "19") (name "/LCD_RX") (class "Default")
      (node (ref "P2") (pin "4") (pinfunction "4_4") (pintype "passive"))
      (node (ref "U1") (pin "43") (pinfunction "PA10/USART1_RX/TIM1_CH3_43") (pintype "passive"))
    )
    (net (code "20") (name "/LCD_TX") (class "Default")
      (node (ref "P2") (pin "3") (pinfunction "3_3") (pintype "passive"))
      (node (ref "U1") (pin "42") (pinfunction "PA9/USART1_TX/TIM1_CH2_42") (pintype "passive"))
    )
    (net (code "21") (name "/LEVEL_DATA") (class "Default")
      (node (ref "P3") (pin "2") (pinfunction "2_2") (pintype "passive"))
      (node (ref "U1") (pin "58") (pinfunction "PB6/I2C1_SCL/TIM4_CH1_58") (pintype "passive"))
    )
    (net (code "22") (name "/LEVEL_EN") (class "Default")
      (node (ref "P3") (pin "3") (pinfunction "3_3") (pintype "passive"))
      (node (ref "U1") (pin "59") (pinfunction "PB7/I2C1_SDA/FSMC_NADV/TIM4_CH2_59") (pintype "passive"))
    )
    (net (code "23") (name "/MODEL_FAN") (class "Default")
      (node (ref "RP1") (pin "4") (pinfunction "1_4") (pintype "passive"))
      (node (ref "U1") (pin "55") (pinfunction "PB3/JTDO/TRACESWO/SPI3_SCK/I2S3_CK_55") (pintype "passive"))
      (node (ref "U2") (pin "2") (pinfunction "A0_2") (pintype "passive"))
    )
    (net (code "24") (name "/MODEL_FAN'") (class "Default")
      (node (ref "R22") (pin "1") (pinfunction "1_1") (pintype "passive"))
      (node (ref "RP2") (pin "8") (pinfunction "1_8") (pintype "passive"))
      (node (ref "U9") (pin "1") (pinfunction "G1_1") (pintype "passive"))
    )
    (net (code "25") (name "/NOZZLE_HEATER") (class "Default")
      (node (ref "RP1") (pin "2") (pinfunction "1_2") (pintype "passive"))
      (node (ref "U1") (pin "57") (pinfunction "PB5/I2C1_SMBAI/SPI3_MOSI/I2S3_SD_57") (pintype "passive"))
      (node (ref "U2") (pin "4") (pinfunction "A2_4") (pintype "passive"))
    )
    (net (code "26") (name "/NOZZLE_HEATER'") (class "Default")
      (node (ref "Q1") (pin "1") (pinfunction "G_1") (pintype "passive"))
      (node (ref "R23") (pin "1") (pinfunction "1_1") (pintype "passive"))
      (node (ref "RP2") (pin "6") (pinfunction "1_6") (pintype "passive"))
    )
    (net (code "27") (name "/NOZZLE_TEMP") (class "Default")
      (node (ref "C10") (pin "1") (pinfunction "1_1") (pintype "passive"))
      (node (ref "P7") (pin "1") (pinfunction "1_1") (pintype "passive"))
      (node (ref "R5") (pin "1") (pinfunction "1_1") (pintype "passive"))
      (node (ref "U1") (pin "11") (pinfunction "PC3/ADC123_IN13_11") (pintype "passive"))
    )
    (net (code "28") (name "/SD_CK") (class "Default")
      (node (ref "P5") (pin "5") (pinfunction "CLK_5") (pintype "passive"))
      (node (ref "U1") (pin "53") (pinfunction "PC12/UART5_TX/SDIO_CK_53") (pintype "passive"))
    )
    (net (code "29") (name "/SD_CMD") (class "Default")
      (node (ref "P5") (pin "2") (pinfunction "CMD_2") (pintype "passive"))
      (node (ref "RP4") (pin "3") (pinfunction "1_3") (pintype "passive"))
      (node (ref "U1") (pin "54") (pinfunction "PD2/TIM3_ETR/UART5_RX/SDIO_CMD_54") (pintype "passive"))
    )
    (net (code "30") (name "/SD_D0") (class "Default")
      (node (ref "P5") (pin "7") (pinfunction "D0_7") (pintype "passive"))
      (node (ref "RP3") (pin "2") (pinfunction "1_2") (pintype "passive"))
      (node (ref "U1") (pin "39") (pinfunction "PC8/TIM8_CH3/SDIO_D0_39") (pintype "passive"))
    )
    (net (code "31") (name "/SD_D1") (class "Default")
      (node (ref "P5") (pin "8") (pinfunction "D1_8") (pintype "passive"))
      (node (ref "RP3") (pin "3") (pinfunction "1_3") (pintype "passive"))
      (node (ref "U1") (pin "40") (pinfunction "PC9/TIM8_CH4/SDIO_D1_40") (pintype "passive"))
    )
    (net (code "32") (name "/SD_D2") (class "Default")
      (node (ref "P5") (pin "9") (pinfunction "D2_9") (pintype "passive"))
      (node (ref "RP4") (pin "1") (pinfunction "1_1") (pintype "passive"))
      (node (ref "U1") (pin "51") (pinfunction "PC10/UART4_TX/SDIO_D2_51") (pintype "passive"))
    )
    (net (code "33") (name "/SD_D3") (class "Default")
      (node (ref "P5") (pin "1") (pinfunction "CD/D3_1") (pintype "passive"))
      (node (ref "RP4") (pin "2") (pinfunction "1_2") (pintype "passive"))
      (node (ref "U1") (pin "52") (pinfunction "PC11/UART4_RX/SDIO_D3_52") (pintype "passive"))
    )
    (net (code "34") (name "/SD_DETECT") (class "Default")
      (node (ref "P5") (pin "10") (pinfunction "CD_10") (pintype "passive"))
      (node (ref "RP4") (pin "4") (pinfunction "1_4") (pintype "passive"))
      (node (ref "U1") (pin "50") (pinfunction "PA15/JTDI/SPI3_NSS/I2S3_WS_50") (pintype "passive"))
    )
    (net (code "35") (name "/SD_WP") (class "Default")
      (node (ref "P5") (pin "11") (pinfunction "WP_11") (pintype "passive"))
      (node (ref "RP3") (pin "4") (pinfunction "1_4") (pintype "passive"))
      (node (ref "U1") (pin "41") (pinfunction "PA8/USART1_CK/TIM1_CH1/MCO_41") (pintype "passive"))
    )
    (net (code "36") (name "/SERIAL_D+") (class "Default")
      (node (ref "P1") (pin "3") (pinfunction "D+_3") (pintype "passive"))
      (node (ref "U3") (pin "5") (pinfunction "UD+_5") (pintype "passive"))
      (node (ref "U4") (pin "3") (pinfunction "IN_3") (pintype "passive"))
    )
    (net (code "37") (name "/SERIAL_D-") (class "Default")
      (node (ref "P1") (pin "2") (pinfunction "D-_2") (pintype "passive"))
      (node (ref "U3") (pin "6") (pinfunction "UD-_6") (pintype "passive"))
      (node (ref "U4") (pin "2") (pinfunction "IN_2") (pintype "passive"))
    )
    (net (code "38") (name "/SERIAL_RX") (class "Default")
      (node (ref "U1") (pin "17") (pinfunction "PA3/USART2_RX/ADC123_IN3/TIM5_CH4/TIM2_CH4_17") (pintype "passive"))
      (node (ref "U3") (pin "2") (pinfunction "TXD_2") (pintype "passive"))
    )
    (net (code "39") (name "/SERIAL_TX") (class "Default")
      (node (ref "U1") (pin "16") (pinfunction "PA2/USART2_TX/ADC123_IN2/TIM5_CH3/TIM2_CH3_16") (pintype "passive"))
      (node (ref "U3") (pin "3") (pinfunction "RXD_3") (pintype "passive"))
    )
    (net (code "40") (name "/STEP_E") (class "Default")
      (node (ref "U1") (pin "21") (pinfunction "PA5/SPI1_SCK/DAC_OUT2/ADC12_IN5_21") (pintype "passive"))
      (node (ref "U15") (pin "16") (pinfunction "STEP_16") (pintype "passive"))
    )
    (net (code "41") (name "/STEP_X") (class "Default")
      (node (ref "U1") (pin "34") (pinfunction "PB13/SPI2_SCK/I2S2_CK/USART3_CTS/TIM1_CH1N_34") (pintype "passive"))
      (node (ref "U11") (pin "16") (pinfunction "STEP_16") (pintype "passive"))
    )
    (net (code "42") (name "/STEP_Y") (class "Default")
      (node (ref "U1") (pin "28") (pinfunction "PB2/BOOT1_28") (pintype "passive"))
      (node (ref "U12") (pin "16") (pinfunction "STEP_16") (pintype "passive"))
    )
    (net (code "43") (name "/STEP_Z") (class "Default")
      (node (ref "U1") (pin "24") (pinfunction "PC4/ADC12_IN14_24") (pintype "passive"))
      (node (ref "U13") (pin "16") (pinfunction "STEP_16") (pintype "passive"))
      (node (ref "U14") (pin "16") (pinfunction "STEP_16") (pintype "passive"))
    )
    (net (code "44") (name "/ST_CLK") (class "Default")
      (node (ref "P4") (pin "3") (pinfunction "3_3") (pintype "passive"))
      (node (ref "U1") (pin "49") (pinfunction "PA14/JTCK/SWCLK_49") (pintype "passive"))
    )
    (net (code "45") (name "/ST_RST") (class "Default")
      (node (ref "C4") (pin "1") (pinfunction "1_1") (pintype "passive"))
      (node (ref "R3") (pin "1") (pinfunction "1_1") (pintype "passive"))
      (node (ref "U1") (pin "7") (pinfunction "NRST_7") (pintype "passive"))
    )
    (net (code "46") (name "/ST_SWD") (class "Default")
      (node (ref "P4") (pin "2") (pinfunction "2_2") (pintype "passive"))
      (node (ref "U1") (pin "46") (pinfunction "PA13/JTMS/SWDIO_46") (pintype "passive"))
    )
    (net (code "47") (name "/VCC_SERIAL") (class "Default")
      (node (ref "C1") (pin "1") (pinfunction "1_1") (pintype "passive"))
      (node (ref "D1") (pin "1") (pinfunction "A_1") (pintype "passive"))
      (node (ref "P1") (pin "1") (pinfunction "VCC_1") (pintype "passive"))
      (node (ref "U4") (pin "4") (pinfunction "VCC_4") (pintype "passive"))
    )
    (net (code "48") (name "3V3") (class "Default")
      (node (ref "C13") (pin "1") (pinfunction "1_1") (pintype "passive"))
      (node (ref "C16") (pin "1") (pinfunction "1_1") (pintype "passive"))
      (node (ref "C17") (pin "1") (pinfunction "1_1") (pintype "passive"))
      (node (ref "C18") (pin "1") (pinfunction "1_1") (pintype "passive"))
      (node (ref "C19") (pin "1") (pinfunction "1_1") (pintype "passive"))
      (node (ref "C2") (pin "1") (pinfunction "1_1") (pintype "passive"))
      (node (ref "C27") (pin "1") (pinfunction "1_1") (pintype "passive"))
      (node (ref "C28") (pin "1") (pinfunction "1_1") (pintype "passive"))
      (node (ref "C31") (pin "1") (pinfunction "1_1") (pintype "passive"))
      (node (ref "C9") (pin "1") (pinfunction "1_1") (pintype "passive"))
      (node (ref "P20") (pin "1") (pinfunction "1_1") (pintype "passive"))
      (node (ref "P3") (pin "1") (pinfunction "1_1") (pintype "passive"))
      (node (ref "P4") (pin "1") (pinfunction "1_1") (pintype "passive"))
      (node (ref "P5") (pin "4") (pinfunction "VDD_4") (pintype "passive"))
      (node (ref "R15") (pin "2") (pinfunction "2_2") (pintype "passive"))
      (node (ref "R16") (pin "2") (pinfunction "2_2") (pintype "passive"))
      (node (ref "R25") (pin "2") (pinfunction "2_2") (pintype "passive"))
      (node (ref "R26") (pin "2") (pinfunction "2_2") (pintype "passive"))
      (node (ref "R27") (pin "2") (pinfunction "2_2") (pintype "passive"))
      (node (ref "R28") (pin "2") (pinfunction "2_2") (pintype "passive"))
      (node (ref "R29") (pin "2") (pinfunction "2_2") (pintype "passive"))
      (node (ref "R3") (pin "2") (pinfunction "2_2") (pintype "passive"))
      (node (ref "R30") (pin "1") (pinfunction "1_1") (pintype "passive"))
      (node (ref "R32") (pin "1") (pinfunction "1_1") (pintype "passive"))
      (node (ref "R34") (pin "1") (pinfunction "1_1") (pintype "passive"))
      (node (ref "R36") (pin "1") (pinfunction "1_1") (pintype "passive"))
      (node (ref "R38") (pin "1") (pinfunction "1_1") (pintype "passive"))
      (node (ref "R45") (pin "2") (pinfunction "2_2") (pintype "passive"))
      (node (ref "R46") (pin "2") (pinfunction "2_2") (pintype "passive"))
      (node (ref "R5") (pin "2") (pinfunction "2_2") (pintype "passive"))
      (node (ref "R6") (pin "2") (pinfunction "2_2") (pintype "passive"))
      (node (ref "R7") (pin "2") (pinfunction "2_2") (pintype "passive"))
      (node (ref "RP3") (pin "5") (pinfunction "1_5") (pintype "passive"))
      (node (ref "RP3") (pin "6") (pinfunction "1_6") (pintype "passive"))
      (node (ref "RP3") (pin "7") (pinfunction "1_7") (pintype "passive"))
      (node (ref "RP3") (pin "8") (pinfunction "1_8") (pintype "passive"))
      (node (ref "RP4") (pin "5") (pinfunction "1_5") (pintype "passive"))
      (node (ref "RP4") (pin "6") (pinfunction "1_6") (pintype "passive"))
      (node (ref "RP4") (pin "7") (pinfunction "1_7") (pintype "passive"))
      (node (ref "RP4") (pin "8") (pinfunction "1_8") (pintype "passive"))
      (node (ref "RP5") (pin "1") (pinfunction "1_1") (pintype "passive"))
      (node (ref "RP5") (pin "2") (pinfunction "1_2") (pintype "passive"))
      (node (ref "RP5") (pin "4") (pinfunction "1_4") (pintype "passive"))
      (node (ref "RP6") (pin "1") (pinfunction "1_1") (pintype "passive"))
      (node (ref "RP6") (pin "2") (pinfunction "1_2") (pintype "passive"))
      (node (ref "RP6") (pin "4") (pinfunction "1_4") (pintype "passive"))
      (node (ref "RP7") (pin "1") (pinfunction "1_1") (pintype "passive"))
      (node (ref "RP7") (pin "2") (pinfunction "1_2") (pintype "passive"))
      (node (ref "RP7") (pin "4") (pinfunction "1_4") (pintype "passive"))
      (node (ref "RP8") (pin "1") (pinfunction "1_1") (pintype "passive"))
      (node (ref "RP8") (pin "2") (pinfunction "1_2") (pintype "passive"))
      (node (ref "RP8") (pin "4") (pinfunction "1_4") (pintype "passive"))
      (node (ref "RP9") (pin "1") (pinfunction "1_1") (pintype "passive"))
      (node (ref "RP9") (pin "2") (pinfunction "1_2") (pintype "passive"))
      (node (ref "RP9") (pin "4") (pinfunction "1_4") (pintype "passive"))
      (node (ref "U1") (pin "19") (pinfunction "VDD_4_19") (pintype "passive"))
      (node (ref "U1") (pin "32") (pinfunction "VDD_1_32") (pintype "passive"))
      (node (ref "U1") (pin "48") (pinfunction "VDD_2_48") (pintype "passive"))
      (node (ref "U1") (pin "64") (pinfunction "VDD_3_64") (pintype "passive"))
      (node (ref "U10") (pin "4") (pinfunction "VCC_4") (pintype "passive"))
      (node (ref "U11") (pin "10") (pinfunction "MS2_10") (pintype "passive"))
      (node (ref "U11") (pin "15") (pinfunction "VCC_IO_15") (pintype "passive"))
      (node (ref "U11") (pin "9") (pinfunction "MS1_9") (pintype "passive"))
      (node (ref "U12") (pin "10") (pinfunction "MS2_10") (pintype "passive"))
      (node (ref "U12") (pin "15") (pinfunction "VCC_IO_15") (pintype "passive"))
      (node (ref "U12") (pin "9") (pinfunction "MS1_9") (pintype "passive"))
      (node (ref "U13") (pin "10") (pinfunction "MS2_10") (pintype "passive"))
      (node (ref "U13") (pin "15") (pinfunction "VCC_IO_15") (pintype "passive"))
      (node (ref "U13") (pin "9") (pinfunction "MS1_9") (pintype "passive"))
      (node (ref "U14") (pin "10") (pinfunction "MS2_10") (pintype "passive"))
      (node (ref "U14") (pin "15") (pinfunction "VCC_IO_15") (pintype "passive"))
      (node (ref "U14") (pin "9") (pinfunction "MS1_9") (pintype "passive"))
      (node (ref "U15") (pin "10") (pinfunction "MS2_10") (pintype "passive"))
      (node (ref "U15") (pin "15") (pinfunction "VCC_IO_15") (pintype "passive"))
      (node (ref "U15") (pin "9") (pinfunction "MS1_9") (pintype "passive"))
      (node (ref "U3") (pin "16") (pinfunction "VCC_16") (pintype "passive"))
      (node (ref "U3") (pin "4") (pinfunction "V3_4") (pintype "passive"))
      (node (ref "U5") (pin "6") (pinfunction "VDD_6") (pintype "passive"))
      (node (ref "U8") (pin "2") (pinfunction "VOUT_2") (pintype "passive"))
    )
    (net (code "49") (name "5V") (class "Default")
      (node (ref "C20") (pin "1") (pinfunction "1_1") (pintype "passive"))
      (node (ref "C25") (pin "1") (pinfunction "1_1") (pintype "passive"))
      (node (ref "C26") (pin "1") (pinfunction "1_1") (pintype "passive"))
      (node (ref "C29") (pin "1") (pinfunction "1_1") (pintype "passive"))
      (node (ref "C3") (pin "1") (pinfunction "1_1") (pintype "passive"))
      (node (ref "D1") (pin "2") (pinfunction "K_2") (pintype "passive"))
      (node (ref "L1") (pin "2") (pinfunction "2_2") (pintype "passive"))
      (node (ref "P2") (pin "1") (pinfunction "1_1") (pintype "passive"))
      (node (ref "R13") (pin "2") (pinfunction "2_2") (pintype "passive"))
      (node (ref "R14") (pin "2") (pinfunction "2_2") (pintype "passive"))
      (node (ref "R2") (pin "2") (pinfunction "2_2") (pintype "passive"))
      (node (ref "U2") (pin "20") (pinfunction "VCC_20") (pintype "passive"))
      (node (ref "U6") (pin "6") (pinfunction "VDD_6") (pintype "passive"))
      (node (ref "U8") (pin "3") (pinfunction "VIN_3") (pintype "passive"))
    )
    (net (code "50") (name "GND") (class "Default")
      (node (ref "C1") (pin "2") (pinfunction "2_2") (pintype "passive"))
      (node (ref "C10") (pin "2") (pinfunction "2_2") (pintype "passive"))
      (node (ref "C11") (pin "2") (pinfunction "2_2") (pintype "passive"))
      (node (ref "C12") (pin "2") (pinfunction "2_2") (pintype "passive"))
      (node (ref "C13") (pin "2") (pinfunction "2_2") (pintype "passive"))
      (node (ref "C14") (pin "2") (pinfunction "2_2") (pintype "passive"))
      (node (ref "C15") (pin "2") (pinfunction "2_2") (pintype "passive"))
      (node (ref "C16") (pin "2") (pinfunction "2_2") (pintype "passive"))
      (node (ref "C17") (pin "2") (pinfunction "2_2") (pintype "passive"))
      (node (ref "C18") (pin "2") (pinfunction "2_2") (pintype "passive"))
      (node (ref "C19") (pin "2") (pinfunction "2_2") (pintype "passive"))
      (node (ref "C2") (pin "2") (pinfunction "2_2") (pintype "passive"))
      (node (ref "C20") (pin "2") (pinfunction "2_2") (pintype "passive"))
      (node (ref "C22") (pin "2") (pinfunction "2_2") (pintype "passive"))
      (node (ref "C23") (pin "2") (pinfunction "2_2") (pintype "passive"))
      (node (ref "C25") (pin "2") (pinfunction "2_2") (pintype "passive"))
      (node (ref "C26") (pin "2") (pinfunction "2_2") (pintype "passive"))
      (node (ref "C27") (pin "2") (pinfunction "2_2") (pintype "passive"))
      (node (ref "C28") (pin "2") (pinfunction "2_2") (pintype "passive"))
      (node (ref "C29") (pin "2") (pinfunction "2_2") (pintype "passive"))
      (node (ref "C3") (pin "2") (pinfunction "2_2") (pintype "passive"))
      (node (ref "C30") (pin "2") (pinfunction "2_2") (pintype "passive"))
      (node (ref "C31") (pin "2") (pinfunction "2_2") (pintype "passive"))
      (node (ref "C37") (pin "2") (pinfunction "2_2") (pintype "passive"))
      (node (ref "C38") (pin "2") (pinfunction "2_2") (pintype "passive"))
      (node (ref "C39") (pin "2") (pinfunction "2_2") (pintype "passive"))
      (node (ref "C4") (pin "2") (pinfunction "2_2") (pintype "passive"))
      (node (ref "C40") (pin "2") (pinfunction "2_2") (pintype "passive"))
      (node (ref "C41") (pin "2") (pinfunction "2_2") (pintype "passive"))
      (node (ref "C42") (pin "2") (pinfunction "2_2") (pintype "passive"))
      (node (ref "C43") (pin "2") (pinfunction "2_2") (pintype "passive"))
      (node (ref "C44") (pin "2") (pinfunction "2_2") (pintype "passive"))
      (node (ref "C45") (pin "2") (pinfunction "2_2") (pintype "passive"))
      (node (ref "C46") (pin "2") (pinfunction "2_2") (pintype "passive"))
      (node (ref "C47") (pin "2") (pinfunction "2_2") (pintype "passive"))
      (node (ref "C48") (pin "2") (pinfunction "2_2") (pintype "passive"))
      (node (ref "C49") (pin "2") (pinfunction "2_2") (pintype "passive"))
      (node (ref "C5") (pin "2") (pinfunction "2_2") (pintype "passive"))
      (node (ref "C50") (pin "2") (pinfunction "2_2") (pintype "passive"))
      (node (ref "C51") (pin "2") (pinfunction "2_2") (pintype "passive"))
      (node (ref "C57") (pin "2") (pinfunction "2_2") (pintype "passive"))
      (node (ref "C58") (pin "2") (pinfunction "2_2") (pintype "passive"))
      (node (ref "C59") (pin "2") (pinfunction "2_2") (pintype "passive"))
      (node (ref "C6") (pin "2") (pinfunction "2_2") (pintype "passive"))
      (node (ref "C60") (pin "2") (pinfunction "2_2") (pintype "passive"))
      (node (ref "C61") (pin "2") (pinfunction "2_2") (pintype "passive"))
      (node (ref "C62") (pin "2") (pinfunction "2_2") (pintype "passive"))
      (node (ref "C63") (pin "2") (pinfunction "2_2") (pintype "passive"))
      (node (ref "C7") (pin "2") (pinfunction "2_2") (pintype "passive"))
      (node (ref "C9") (pin "2") (pinfunction "2_2") (pintype "passive"))
      (node (ref "D2") (pin "1") (pinfunction "A_1") (pintype "passive"))
      (node (ref "D5") (pin "2") (pinfunction "K_2") (pintype "passive"))
      (node (ref "P1") (pin "5") (pinfunction "GND_5") (pintype "passive"))
      (node (ref "P13") (pin "1") (pinfunction "1_1") (pintype "passive"))
      (node (ref "P14") (pin "1") (pinfunction "1_1") (pintype "passive"))
      (node (ref "P15") (pin "5") (pinfunction "5_5") (pintype "passive"))
      (node (ref "P16") (pin "5") (pinfunction "5_5") (pintype "passive"))
      (node (ref "P2") (pin "6") (pinfunction "6_6") (pintype "passive"))
      (node (ref "P20") (pin "3") (pinfunction "3_3") (pintype "passive"))
      (node (ref "P3") (pin "4") (pinfunction "4_4") (pintype "passive"))
      (node (ref "P4") (pin "4") (pinfunction "4_4") (pintype "passive"))
      (node (ref "P5") (pin "12") (pinfunction "SHELL_12") (pintype "passive"))
      (node (ref "P5") (pin "3") (pinfunction "VSS_3") (pintype "passive"))
      (node (ref "P5") (pin "6") (pinfunction "VSS_6") (pintype "passive"))
      (node (ref "P7") (pin "2") (pinfunction "2_2") (pintype "passive"))
      (node (ref "P8") (pin "2") (pinfunction "2_2") (pintype "passive"))
      (node (ref "P9") (pin "2") (pinfunction "2_2") (pintype "passive"))
      (node (ref "Q1") (pin "3") (pinfunction "S_3") (pintype "passive"))
      (node (ref "Q2") (pin "3") (pinfunction "S_3") (pintype "passive"))
      (node (ref "R1") (pin "2") (pinfunction "2_2") (pintype "passive"))
      (node (ref "R17") (pin "2") (pinfunction "2_2") (pintype "passive"))
      (node (ref "R18") (pin "2") (pinfunction "2_2") (pintype "passive"))
      (node (ref "R19") (pin "2") (pinfunction "2_2") (pintype "passive"))
      (node (ref "R22") (pin "2") (pinfunction "2_2") (pintype "passive"))
      (node (ref "R23") (pin "2") (pinfunction "2_2") (pintype "passive"))
      (node (ref "R24") (pin "2") (pinfunction "2_2") (pintype "passive"))
      (node (ref "R31") (pin "2") (pinfunction "2_2") (pintype "passive"))
      (node (ref "R33") (pin "2") (pinfunction "2_2") (pintype "passive"))
      (node (ref "R35") (pin "2") (pinfunction "2_2") (pintype "passive"))
      (node (ref "R37") (pin "2") (pinfunction "2_2") (pintype "passive"))
      (node (ref "R39") (pin "2") (pinfunction "2_2") (pintype "passive"))
      (node (ref "R4") (pin "2") (pinfunction "2_2") (pintype "passive"))
      (node (ref "R40") (pin "2") (pinfunction "2_2") (pintype "passive"))
      (node (ref "R41") (pin "2") (pinfunction "2_2") (pintype "passive"))
      (node (ref "R42") (pin "2") (pinfunction "2_2") (pintype "passive"))
      (node (ref "R43") (pin "2") (pinfunction "2_2") (pintype "passive"))
      (node (ref "R44") (pin "2") (pinfunction "2_2") (pintype "passive"))
      (node (ref "R8") (pin "2") (pinfunction "2_2") (pintype "passive"))
      (node (ref "RP1") (pin "5") (pinfunction "1_5") (pintype "passive"))
      (node (ref "RP1") (pin "6") (pinfunction "1_6") (pintype "passive"))
      (node (ref "RP1") (pin "7") (pinfunction "1_7") (pintype "passive"))
      (node (ref "RP1") (pin "8") (pinfunction "1_8") (pintype "passive"))
      (node (ref "RP5") (pin "3") (pinfunction "1_3") (pintype "passive"))
      (node (ref "RP6") (pin "3") (pinfunction "1_3") (pintype "passive"))
      (node (ref "RP7") (pin "3") (pinfunction "1_3") (pintype "passive"))
      (node (ref "RP8") (pin "3") (pinfunction "1_3") (pintype "passive"))
      (node (ref "RP9") (pin "3") (pinfunction "1_3") (pintype "passive"))
      (node (ref "U1") (pin "18") (pinfunction "VSS_4_18") (pintype "passive"))
      (node (ref "U1") (pin "31") (pinfunction "VSS_1_31") (pintype "passive"))
      (node (ref "U1") (pin "47") (pinfunction "VSS_2_47") (pintype "passive"))
      (node (ref "U1") (pin "63") (pinfunction "VSS_3_63") (pintype "passive"))
      (node (ref "U10") (pin "2") (pinfunction "GND_2") (pintype "passive"))
      (node (ref "U10") (pin "5") (pinfunction "WP_5") (pintype "passive"))
      (node (ref "U11") (pin "0") (pinfunction "GND_0") (pintype "passive"))
      (node (ref "U11") (pin "18") (pinfunction "GND_18") (pintype "passive"))
      (node (ref "U11") (pin "20") (pinfunction "NC_20") (pintype "passive"))
      (node (ref "U11") (pin "25") (pinfunction "NC_25") (pintype "passive"))
      (node (ref "U11") (pin "3") (pinfunction "GND_3") (pintype "passive"))
      (node (ref "U11") (pin "7") (pinfunction "NC_7") (pintype "passive"))
      (node (ref "U12") (pin "0") (pinfunction "GND_0") (pintype "passive"))
      (node (ref "U12") (pin "18") (pinfunction "GND_18") (pintype "passive"))
      (node (ref "U12") (pin "20") (pinfunction "NC_20") (pintype "passive"))
      (node (ref "U12") (pin "25") (pinfunction "NC_25") (pintype "passive"))
      (node (ref "U12") (pin "3") (pinfunction "GND_3") (pintype "passive"))
      (node (ref "U12") (pin "7") (pinfunction "NC_7") (pintype "passive"))
      (node (ref "U13") (pin "0") (pinfunction "GND_0") (pintype "passive"))
      (node (ref "U13") (pin "18") (pinfunction "GND_18") (pintype "passive"))
      (node (ref "U13") (pin "20") (pinfunction "NC_20") (pintype "passive"))
      (node (ref "U13") (pin "25") (pinfunction "NC_25") (pintype "passive"))
      (node (ref "U13") (pin "3") (pinfunction "GND_3") (pintype "passive"))
      (node (ref "U13") (pin "7") (pinfunction "NC_7") (pintype "passive"))
      (node (ref "U14") (pin "0") (pinfunction "GND_0") (pintype "passive"))
      (node (ref "U14") (pin "18") (pinfunction "GND_18") (pintype "passive"))
      (node (ref "U14") (pin "20") (pinfunction "NC_20") (pintype "passive"))
      (node (ref "U14") (pin "25") (pinfunction "NC_25") (pintype "passive"))
      (node (ref "U14") (pin "3") (pinfunction "GND_3") (pintype "passive"))
      (node (ref "U14") (pin "7") (pinfunction "NC_7") (pintype "passive"))
      (node (ref "U15") (pin "0") (pinfunction "GND_0") (pintype "passive"))
      (node (ref "U15") (pin "18") (pinfunction "GND_18") (pintype "passive"))
      (node (ref "U15") (pin "20") (pinfunction "NC_20") (pintype "passive"))
      (node (ref "U15") (pin "25") (pinfunction "NC_25") (pintype "passive"))
      (node (ref "U15") (pin "3") (pinfunction "GND_3") (pintype "passive"))
      (node (ref "U15") (pin "7") (pinfunction "NC_7") (pintype "passive"))
      (node (ref "U2") (pin "10") (pinfunction "GND_10") (pintype "passive"))
      (node (ref "U3") (pin "1") (pinfunction "GND_1") (pintype "passive"))
      (node (ref "U4") (pin "1") (pinfunction "GND_1") (pintype "passive"))
      (node (ref "U5") (pin "8") (pinfunction "GND_8") (pintype "passive"))
      (node (ref "U6") (pin "7") (pinfunction "GND_7") (pintype "passive"))
      (node (ref "U7") (pin "0") (pinfunction "GND_0") (pintype "passive"))
      (node (ref "U7") (pin "4") (pinfunction "GND_4") (pintype "passive"))
      (node (ref "U8") (pin "1") (pinfunction "GND_1") (pintype "passive"))
      (node (ref "U9") (pin "2") (pinfunction "S2_2") (pintype "passive"))
      (node (ref "U9") (pin "5") (pinfunction "S1_5") (pintype "passive"))
      (node (ref "VR1") (pin "3") (pinfunction "3_3") (pintype "passive"))
      (node (ref "VR2") (pin "3") (pinfunction "3_3") (pintype "passive"))
      (node (ref "VR3") (pin "3") (pinfunction "3_3") (pintype "passive"))
      (node (ref "VR4") (pin "3") (pinfunction "3_3") (pintype "passive"))
      (node (ref "VR5") (pin "3") (pinfunction "3_3") (pintype "passive"))
      (node (ref "Y1") (pin "2") (pinfunction "3_2") (pintype "passive"))
    )
    (net (code "51") (name "Net-(C8-Pad2)") (class "Default")
      (node (ref "C8") (pin "2") (pinfunction "2_2") (pintype "passive"))
      (node (ref "R9") (pin "1") (pinfunction "1_1") (pintype "passive"))
    )
    (net (code "52") (name "Net-(C21-Pad2)") (class "Default")
      (node (ref "C21") (pin "2") (pinfunction "2_2") (pintype "passive"))
      (node (ref "R11") (pin "1") (pinfunction "1_1") (pintype "passive"))
    )
    (net (code "53") (name "Net-(C24-Pad2)") (class "Default")
      (node (ref "C24") (pin "2") (pinfunction "2_2") (pintype "passive"))
      (node (ref "R18") (pin "1") (pinfunction "1_1") (pintype "passive"))
    )
    (net (code "54") (name "Net-(C62-Pad1)") (class "Default")
      (node (ref "C62") (pin "1") (pinfunction "1_1") (pintype "passive"))
      (node (ref "P15") (pin "6") (pinfunction "6_6") (pintype "passive"))
      (node (ref "R45") (pin "1") (pinfunction "1_1") (pintype "passive"))
      (node (ref "R47") (pin "1") (pinfunction "1_1") (pintype "passive"))
    )
    (net (code "55") (name "Net-(C63-Pad1)") (class "Default")
      (node (ref "C63") (pin "1") (pinfunction "1_1") (pintype "passive"))
      (node (ref "P16") (pin "6") (pinfunction "6_6") (pintype "passive"))
      (node (ref "R46") (pin "1") (pinfunction "1_1") (pintype "passive"))
      (node (ref "R48") (pin "1") (pinfunction "1_1") (pintype "passive"))
    )
    (net (code "56") (name "Net-(D2-K)") (class "Default")
      (node (ref "D2") (pin "2") (pinfunction "K_2") (pintype "passive"))
      (node (ref "L1") (pin "1") (pinfunction "1_1") (pintype "passive"))
      (node (ref "R11") (pin "2") (pinfunction "2_2") (pintype "passive"))
      (node (ref "U7") (pin "3") (pinfunction "SW_3") (pintype "passive"))
    )
    (net (code "57") (name "Net-(D3-A)") (class "Default")
      (node (ref "D3") (pin "1") (pinfunction "A_1") (pintype "passive"))
      (node (ref "D6") (pin "2") (pinfunction "K_2") (pintype "passive"))
      (node (ref "P11") (pin "2") (pinfunction "2_2") (pintype "passive"))
      (node (ref "Q1") (pin "2") (pinfunction "D_2") (pintype "passive"))
    )
    (net (code "58") (name "Net-(D4-A)") (class "Default")
      (node (ref "D4") (pin "1") (pinfunction "A_1") (pintype "passive"))
      (node (ref "D7") (pin "2") (pinfunction "K_2") (pintype "passive"))
      (node (ref "P12") (pin "2") (pinfunction "2_2") (pintype "passive"))
      (node (ref "Q2") (pin "2") (pinfunction "D_2") (pintype "passive"))
    )
    (net (code "59") (name "Net-(D5-A)") (class "Default")
      (node (ref "D5") (pin "1") (pinfunction "A_1") (pintype "passive"))
      (node (ref "R14") (pin "1") (pinfunction "1_1") (pintype "passive"))
    )
    (net (code "60") (name "Net-(D6-A)") (class "Default")
      (node (ref "D6") (pin "1") (pinfunction "A_1") (pintype "passive"))
      (node (ref "R20") (pin "1") (pinfunction "1_1") (pintype "passive"))
    )
    (net (code "61") (name "Net-(D7-A)") (class "Default")
      (node (ref "D7") (pin "1") (pinfunction "A_1") (pintype "passive"))
      (node (ref "R21") (pin "1") (pinfunction "1_1") (pintype "passive"))
    )
    (net (code "62") (name "Net-(R30-Pad2)") (class "Default")
      (node (ref "R30") (pin "2") (pinfunction "2_2") (pintype "passive"))
      (node (ref "VR1") (pin "1") (pinfunction "1_1") (pintype "passive"))
    )
    (net (code "63") (name "Net-(R32-Pad2)") (class "Default")
      (node (ref "R32") (pin "2") (pinfunction "2_2") (pintype "passive"))
      (node (ref "VR2") (pin "1") (pinfunction "1_1") (pintype "passive"))
    )
    (net (code "64") (name "Net-(R34-Pad2)") (class "Default")
      (node (ref "R34") (pin "2") (pinfunction "2_2") (pintype "passive"))
      (node (ref "VR3") (pin "1") (pinfunction "1_1") (pintype "passive"))
    )
    (net (code "65") (name "Net-(R36-Pad2)") (class "Default")
      (node (ref "R36") (pin "2") (pinfunction "2_2") (pintype "passive"))
      (node (ref "VR4") (pin "1") (pinfunction "1_1") (pintype "passive"))
    )
    (net (code "66") (name "Net-(R38-Pad2)") (class "Default")
      (node (ref "R38") (pin "2") (pinfunction "2_2") (pintype "passive"))
      (node (ref "VR5") (pin "1") (pinfunction "1_1") (pintype "passive"))
    )
    (net (code "67") (name "Net-(U1-BOOT0)") (class "Default")
      (node (ref "R4") (pin "1") (pinfunction "1_1") (pintype "passive"))
      (node (ref "U1") (pin "60") (pinfunction "BOOT0_60") (pintype "passive"))
    )
    (net (code "68") (name "Net-(U1-OSC_IN)") (class "Default")
      (node (ref "C5") (pin "1") (pinfunction "1_1") (pintype "passive"))
      (node (ref "U1") (pin "5") (pinfunction "OSC_IN_5") (pintype "passive"))
      (node (ref "Y2") (pin "2") (pinfunction "OSC2_2") (pintype "passive"))
    )
    (net (code "69") (name "Net-(U1-OSC_OUT)") (class "Default")
      (node (ref "C7") (pin "1") (pinfunction "1_1") (pintype "passive"))
      (node (ref "U1") (pin "6") (pinfunction "OSC_OUT_6") (pintype "passive"))
      (node (ref "Y2") (pin "1") (pinfunction "OSC1_1") (pintype "passive"))
    )
    (net (code "70") (name "Net-(U1-VDDA)") (class "Default")
      (node (ref "C14") (pin "1") (pinfunction "1_1") (pintype "passive"))
      (node (ref "C15") (pin "1") (pinfunction "1_1") (pintype "passive"))
      (node (ref "R7") (pin "1") (pinfunction "1_1") (pintype "passive"))
      (node (ref "U1") (pin "13") (pinfunction "VDDA_13") (pintype "passive"))
    )
    (net (code "71") (name "Net-(U1-VSSA)") (class "Default")
      (node (ref "R8") (pin "1") (pinfunction "1_1") (pintype "passive"))
      (node (ref "U1") (pin "12") (pinfunction "VSSA_12") (pintype "passive"))
    )
    (net (code "72") (name "Net-(U2-B0)") (class "Default")
      (node (ref "RP2") (pin "1") (pinfunction "1_1") (pintype "passive"))
      (node (ref "U2") (pin "18") (pinfunction "B0_18") (pintype "passive"))
    )
    (net (code "73") (name "Net-(U2-B1)") (class "Default")
      (node (ref "RP2") (pin "2") (pinfunction "1_2") (pintype "passive"))
      (node (ref "U2") (pin "17") (pinfunction "B1_17") (pintype "passive"))
    )
    (net (code "74") (name "Net-(U2-B2)") (class "Default")
      (node (ref "RP2") (pin "3") (pinfunction "1_3") (pintype "passive"))
      (node (ref "U2") (pin "16") (pinfunction "B2_16") (pintype "passive"))
    )
    (net (code "75") (name "Net-(U2-DIR)") (class "Default")
      (node (ref "R2") (pin "1") (pinfunction "1_1") (pintype "passive"))
      (node (ref "U2") (pin "1") (pinfunction "DIR_1") (pintype "passive"))
    )
    (net (code "76") (name "Net-(U2-~{E})") (class "Default")
      (node (ref "R1") (pin "1") (pinfunction "1_1") (pintype "passive"))
      (node (ref "U2") (pin "19") (pinfunction "~{E}_19") (pintype "passive"))
    )
    (net (code "77") (name "Net-(U3-XI)") (class "Default")
      (node (ref "U3") (pin "7") (pinfunction "XI_7") (pintype "passive"))
      (node (ref "Y1") (pin "3") (pinfunction "OSC2_3") (pintype "passive"))
    )
    (net (code "78") (name "Net-(U3-XO)") (class "Default")
      (node (ref "U3") (pin "8") (pinfunction "XO_8") (pintype "passive"))
      (node (ref "Y1") (pin "1") (pinfunction "OSC1_1") (pintype "passive"))
    )
    (net (code "79") (name "Net-(U5-PWM+{slash}DAC)") (class "Default")
      (node (ref "C8") (pin "1") (pinfunction "1_1") (pintype "passive"))
      (node (ref "U5") (pin "7") (pinfunction "PWM+/DAC_7") (pintype "passive"))
    )
    (net (code "80") (name "Net-(U5-PWM-)") (class "Default")
      (node (ref "C12") (pin "1") (pinfunction "1_1") (pintype "passive"))
      (node (ref "U5") (pin "5") (pinfunction "PWM-_5") (pintype "passive"))
    )
    (net (code "81") (name "Net-(U6-+IN)") (class "Default")
      (node (ref "C6") (pin "1") (pinfunction "1_1") (pintype "passive"))
      (node (ref "U6") (pin "2") (pinfunction "BYPASS_2") (pintype "passive"))
      (node (ref "U6") (pin "3") (pinfunction "+IN_3") (pintype "passive"))
    )
    (net (code "82") (name "Net-(U6--IN)") (class "Default")
      (node (ref "R10") (pin "1") (pinfunction "1_1") (pintype "passive"))
      (node (ref "R9") (pin "2") (pinfunction "2_2") (pintype "passive"))
      (node (ref "U6") (pin "4") (pinfunction "-IN_4") (pintype "passive"))
    )
    (net (code "83") (name "Net-(U6-VO1)") (class "Default")
      (node (ref "P6") (pin "1") (pinfunction "1_1") (pintype "passive"))
      (node (ref "R10") (pin "2") (pinfunction "2_2") (pintype "passive"))
      (node (ref "U6") (pin "5") (pinfunction "VO1_5") (pintype "passive"))
    )
    (net (code "84") (name "Net-(U6-VO2)") (class "Default")
      (node (ref "P6") (pin "2") (pinfunction "2_2") (pintype "passive"))
      (node (ref "U6") (pin "8") (pinfunction "VO2_8") (pintype "passive"))
    )
    (net (code "85") (name "Net-(U7-BS)") (class "Default")
      (node (ref "C21") (pin "1") (pinfunction "1_1") (pintype "passive"))
      (node (ref "U7") (pin "1") (pinfunction "BS_1") (pintype "passive"))
    )
    (net (code "86") (name "Net-(U7-COMP)") (class "Default")
      (node (ref "C24") (pin "1") (pinfunction "1_1") (pintype "passive"))
      (node (ref "U7") (pin "6") (pinfunction "COMP_6") (pintype "passive"))
    )
    (net (code "87") (name "Net-(U7-EN)") (class "Default")
      (node (ref "R12") (pin "2") (pinfunction "2_2") (pintype "passive"))
      (node (ref "R17") (pin "1") (pinfunction "1_1") (pintype "passive"))
      (node (ref "U7") (pin "7") (pinfunction "EN_7") (pintype "passive"))
    )
    (net (code "88") (name "Net-(U7-FB)") (class "Default")
      (node (ref "R13") (pin "1") (pinfunction "1_1") (pintype "passive"))
      (node (ref "R19") (pin "1") (pinfunction "1_1") (pintype "passive"))
      (node (ref "U7") (pin "5") (pinfunction "FB_5") (pintype "passive"))
    )
    (net (code "89") (name "Net-(U7-SS)") (class "Default")
      (node (ref "C30") (pin "1") (pinfunction "1_1") (pintype "passive"))
      (node (ref "U7") (pin "8") (pinfunction "SS_8") (pintype "passive"))
    )
    (net (code "90") (name "Net-(U9-D1)") (class "Default")
      (node (ref "P10") (pin "1") (pinfunction "1_1") (pintype "passive"))
      (node (ref "U9") (pin "6") (pinfunction "D1_6") (pintype "passive"))
    )
    (net (code "91") (name "Net-(U11-5VOUT)") (class "Default")
      (node (ref "C57") (pin "1") (pinfunction "1_1") (pintype "passive"))
      (node (ref "U11") (pin "8") (pinfunction "5VOUT_8") (pintype "passive"))
    )
    (net (code "92") (name "Net-(U11-BRA)") (class "Default")
      (node (ref "R31") (pin "1") (pinfunction "1_1") (pintype "passive"))
      (node (ref "U11") (pin "23") (pinfunction "BRA_23") (pintype "passive"))
    )
    (net (code "93") (name "Net-(U11-BRB)") (class "Default")
      (node (ref "R40") (pin "1") (pinfunction "1_1") (pintype "passive"))
      (node (ref "U11") (pin "27") (pinfunction "BRB_27") (pintype "passive"))
    )
    (net (code "94") (name "Net-(U11-CLK)") (class "Default")
      (node (ref "RP5") (pin "6") (pinfunction "1_6") (pintype "passive"))
      (node (ref "U11") (pin "13") (pinfunction "CLK_13") (pintype "passive"))
    )
    (net (code "95") (name "Net-(U11-CPI)") (class "Default")
      (node (ref "C32") (pin "2") (pinfunction "2_2") (pintype "passive"))
      (node (ref "U11") (pin "5") (pinfunction "CPI_5") (pintype "passive"))
    )
    (net (code "96") (name "Net-(U11-CPO)") (class "Default")
      (node (ref "C32") (pin "1") (pinfunction "1_1") (pintype "passive"))
      (node (ref "U11") (pin "4") (pinfunction "CPO_4") (pintype "passive"))
    )
    (net (code "97") (name "Net-(U11-DIAG)") (class "Default")
      (node (ref "RP5") (pin "8") (pinfunction "1_8") (pintype "passive"))
      (node (ref "U11") (pin "11") (pinfunction "DIAG_11") (pintype "passive"))
    )
    (net (code "98") (name "Net-(U11-INDEX)") (class "Default")
      (node (ref "RP5") (pin "7") (pinfunction "1_7") (pintype "passive"))
      (node (ref "U11") (pin "12") (pinfunction "INDEX_12") (pintype "passive"))
    )
    (net (code "99") (name "Net-(U11-OA1)") (class "Default")
      (node (ref "P15") (pin "2") (pinfunction "2_2") (pintype "passive"))
      (node (ref "U11") (pin "24") (pinfunction "OA1_24") (pintype "passive"))
    )
    (net (code "100") (name "Net-(U11-OA2)") (class "Default")
      (node (ref "P15") (pin "1") (pinfunction "1_1") (pintype "passive"))
      (node (ref "U11") (pin "21") (pinfunction "OA2_21") (pintype "passive"))
    )
    (net (code "101") (name "Net-(U11-OB1)") (class "Default")
      (node (ref "P15") (pin "3") (pinfunction "3_3") (pintype "passive"))
      (node (ref "U11") (pin "26") (pinfunction "OB1_26") (pintype "passive"))
    )
    (net (code "102") (name "Net-(U11-OB2)") (class "Default")
      (node (ref "P15") (pin "4") (pinfunction "4_4") (pintype "passive"))
      (node (ref "U11") (pin "1") (pinfunction "OB2_1") (pintype "passive"))
    )
    (net (code "103") (name "Net-(U11-PDN_UART)") (class "Default")
      (node (ref "RP5") (pin "5") (pinfunction "1_5") (pintype "passive"))
      (node (ref "U11") (pin "14") (pinfunction "PDN_UART_14") (pintype "passive"))
    )
    (net (code "104") (name "Net-(U11-VCP)") (class "Default")
      (node (ref "C52") (pin "1") (pinfunction "1_1") (pintype "passive"))
      (node (ref "U11") (pin "6") (pinfunction "VCP_6") (pintype "passive"))
    )
    (net (code "105") (name "Net-(U11-VREF)") (class "Default")
      (node (ref "U11") (pin "17") (pinfunction "VREF_17") (pintype "passive"))
      (node (ref "VR1") (pin "2") (pinfunction "2_2") (pintype "passive"))
    )
    (net (code "106") (name "Net-(U12-5VOUT)") (class "Default")
      (node (ref "C58") (pin "1") (pinfunction "1_1") (pintype "passive"))
      (node (ref "U12") (pin "8") (pinfunction "5VOUT_8") (pintype "passive"))
    )
    (net (code "107") (name "Net-(U12-BRA)") (class "Default")
      (node (ref "R33") (pin "1") (pinfunction "1_1") (pintype "passive"))
      (node (ref "U12") (pin "23") (pinfunction "BRA_23") (pintype "passive"))
    )
    (net (code "108") (name "Net-(U12-BRB)") (class "Default")
      (node (ref "R41") (pin "1") (pinfunction "1_1") (pintype "passive"))
      (node (ref "U12") (pin "27") (pinfunction "BRB_27") (pintype "passive"))
    )
    (net (code "109") (name "Net-(U12-CLK)") (class "Default")
      (node (ref "RP6") (pin "6") (pinfunction "1_6") (pintype "passive"))
      (node (ref "U12") (pin "13") (pinfunction "CLK_13") (pintype "passive"))
    )
    (net (code "110") (name "Net-(U12-CPI)") (class "Default")
      (node (ref "C33") (pin "2") (pinfunction "2_2") (pintype "passive"))
      (node (ref "U12") (pin "5") (pinfunction "CPI_5") (pintype "passive"))
    )
    (net (code "111") (name "Net-(U12-CPO)") (class "Default")
      (node (ref "C33") (pin "1") (pinfunction "1_1") (pintype "passive"))
      (node (ref "U12") (pin "4") (pinfunction "CPO_4") (pintype "passive"))
    )
    (net (code "112") (name "Net-(U12-DIAG)") (class "Default")
      (node (ref "RP6") (pin "8") (pinfunction "1_8") (pintype "passive"))
      (node (ref "U12") (pin "11") (pinfunction "DIAG_11") (pintype "passive"))
    )
    (net (code "113") (name "Net-(U12-INDEX)") (class "Default")
      (node (ref "RP6") (pin "7") (pinfunction "1_7") (pintype "passive"))
      (node (ref "U12") (pin "12") (pinfunction "INDEX_12") (pintype "passive"))
    )
    (net (code "114") (name "Net-(U12-OA1)") (class "Default")
      (node (ref "P16") (pin "2") (pinfunction "2_2") (pintype "passive"))
      (node (ref "U12") (pin "24") (pinfunction "OA1_24") (pintype "passive"))
    )
    (net (code "115") (name "Net-(U12-OA2)") (class "Default")
      (node (ref "P16") (pin "1") (pinfunction "1_1") (pintype "passive"))
      (node (ref "U12") (pin "21") (pinfunction "OA2_21") (pintype "passive"))
    )
    (net (code "116") (name "Net-(U12-OB1)") (class "Default")
      (node (ref "P16") (pin "3") (pinfunction "3_3") (pintype "passive"))
      (node (ref "U12") (pin "26") (pinfunction "OB1_26") (pintype "passive"))
    )
    (net (code "117") (name "Net-(U12-OB2)") (class "Default")
      (node (ref "P16") (pin "4") (pinfunction "4_4") (pintype "passive"))
      (node (ref "U12") (pin "1") (pinfunction "OB2_1") (pintype "passive"))
    )
    (net (code "118") (name "Net-(U12-PDN_UART)") (class "Default")
      (node (ref "RP6") (pin "5") (pinfunction "1_5") (pintype "passive"))
      (node (ref "U12") (pin "14") (pinfunction "PDN_UART_14") (pintype "passive"))
    )
    (net (code "119") (name "Net-(U12-VCP)") (class "Default")
      (node (ref "C53") (pin "1") (pinfunction "1_1") (pintype "passive"))
      (node (ref "U12") (pin "6") (pinfunction "VCP_6") (pintype "passive"))
    )
    (net (code "120") (name "Net-(U12-VREF)") (class "Default")
      (node (ref "U12") (pin "17") (pinfunction "VREF_17") (pintype "passive"))
      (node (ref "VR2") (pin "2") (pinfunction "2_2") (pintype "passive"))
    )
    (net (code "121") (name "Net-(U13-5VOUT)") (class "Default")
      (node (ref "C59") (pin "1") (pinfunction "1_1") (pintype "passive"))
      (node (ref "U13") (pin "8") (pinfunction "5VOUT_8") (pintype "passive"))
    )
    (net (code "122") (name "Net-(U13-BRA)") (class "Default")
      (node (ref "R35") (pin "1") (pinfunction "1_1") (pintype "passive"))
      (node (ref "U13") (pin "23") (pinfunction "BRA_23") (pintype "passive"))
    )
    (net (code "123") (name "Net-(U13-BRB)") (class "Default")
      (node (ref "R42") (pin "1") (pinfunction "1_1") (pintype "passive"))
      (node (ref "U13") (pin "27") (pinfunction "BRB_27") (pintype "passive"))
    )
    (net (code "124") (name "Net-(U13-CLK)") (class "Default")
      (node (ref "RP7") (pin "6") (pinfunction "1_6") (pintype "passive"))
      (node (ref "U13") (pin "13") (pinfunction "CLK_13") (pintype "passive"))
    )
    (net (code "125") (name "Net-(U13-CPI)") (class "Default")
      (node (ref "C34") (pin "2") (pinfunction "2_2") (pintype "passive"))
      (node (ref "U13") (pin "5") (pinfunction "CPI_5") (pintype "passive"))
    )
    (net (code "126") (name "Net-(U13-CPO)") (class "Default")
      (node (ref "C34") (pin "1") (pinfunction "1_1") (pintype "passive"))
      (node (ref "U13") (pin "4") (pinfunction "CPO_4") (pintype "passive"))
    )
    (net (code "127") (name "Net-(U13-DIAG)") (class "Default")
      (node (ref "RP7") (pin "8") (pinfunction "1_8") (pintype "passive"))
      (node (ref "U13") (pin "11") (pinfunction "DIAG_11") (pintype "passive"))
    )
    (net (code "128") (name "Net-(U13-INDEX)") (class "Default")
      (node (ref "RP7") (pin "7") (pinfunction "1_7") (pintype "passive"))
      (node (ref "U13") (pin "12") (pinfunction "INDEX_12") (pintype "passive"))
    )
    (net (code "129") (name "Net-(U13-OA1)") (class "Default")
      (node (ref "P17") (pin "2") (pinfunction "2_2") (pintype "passive"))
      (node (ref "U13") (pin "24") (pinfunction "OA1_24") (pintype "passive"))
    )
    (net (code "130") (name "Net-(U13-OA2)") (class "Default")
      (node (ref "P17") (pin "1") (pinfunction "1_1") (pintype "passive"))
      (node (ref "U13") (pin "21") (pinfunction "OA2_21") (pintype "passive"))
    )
    (net (code "131") (name "Net-(U13-OB1)") (class "Default")
      (node (ref "P17") (pin "3") (pinfunction "3_3") (pintype "passive"))
      (node (ref "U13") (pin "26") (pinfunction "OB1_26") (pintype "passive"))
    )
    (net (code "132") (name "Net-(U13-OB2)") (class "Default")
      (node (ref "P17") (pin "4") (pinfunction "4_4") (pintype "passive"))
      (node (ref "U13") (pin "1") (pinfunction "OB2_1") (pintype "passive"))
    )
    (net (code "133") (name "Net-(U13-PDN_UART)") (class "Default")
      (node (ref "RP7") (pin "5") (pinfunction "1_5") (pintype "passive"))
      (node (ref "U13") (pin "14") (pinfunction "PDN_UART_14") (pintype "passive"))
    )
    (net (code "134") (name "Net-(U13-VCP)") (class "Default")
      (node (ref "C54") (pin "1") (pinfunction "1_1") (pintype "passive"))
      (node (ref "U13") (pin "6") (pinfunction "VCP_6") (pintype "passive"))
    )
    (net (code "135") (name "Net-(U13-VREF)") (class "Default")
      (node (ref "U13") (pin "17") (pinfunction "VREF_17") (pintype "passive"))
      (node (ref "VR3") (pin "2") (pinfunction "2_2") (pintype "passive"))
    )
    (net (code "136") (name "Net-(U14-5VOUT)") (class "Default")
      (node (ref "C60") (pin "1") (pinfunction "1_1") (pintype "passive"))
      (node (ref "U14") (pin "8") (pinfunction "5VOUT_8") (pintype "passive"))
    )
    (net (code "137") (name "Net-(U14-BRA)") (class "Default")
      (node (ref "R37") (pin "1") (pinfunction "1_1") (pintype "passive"))
      (node (ref "U14") (pin "23") (pinfunction "BRA_23") (pintype "passive"))
    )
    (net (code "138") (name "Net-(U14-BRB)") (class "Default")
      (node (ref "R43") (pin "1") (pinfunction "1_1") (pintype "passive"))
      (node (ref "U14") (pin "27") (pinfunction "BRB_27") (pintype "passive"))
    )
    (net (code "139") (name "Net-(U14-CLK)") (class "Default")
      (node (ref "RP8") (pin "6") (pinfunction "1_6") (pintype "passive"))
      (node (ref "U14") (pin "13") (pinfunction "CLK_13") (pintype "passive"))
    )
    (net (code "140") (name "Net-(U14-CPI)") (class "Default")
      (node (ref "C35") (pin "2") (pinfunction "2_2") (pintype "passive"))
      (node (ref "U14") (pin "5") (pinfunction "CPI_5") (pintype "passive"))
    )
    (net (code "141") (name "Net-(U14-CPO)") (class "Default")
      (node (ref "C35") (pin "1") (pinfunction "1_1") (pintype "passive"))
      (node (ref "U14") (pin "4") (pinfunction "CPO_4") (pintype "passive"))
    )
    (net (code "142") (name "Net-(U14-DIAG)") (class "Default")
      (node (ref "RP8") (pin "8") (pinfunction "1_8") (pintype "passive"))
      (node (ref "U14") (pin "11") (pinfunction "DIAG_11") (pintype "passive"))
    )
    (net (code "143") (name "Net-(U14-INDEX)") (class "Default")
      (node (ref "RP8") (pin "7") (pinfunction "1_7") (pintype "passive"))
      (node (ref "U14") (pin "12") (pinfunction "INDEX_12") (pintype "passive"))
    )
    (net (code "144") (name "Net-(U14-OA1)") (class "Default")
      (node (ref "P18") (pin "2") (pinfunction "2_2") (pintype "passive"))
      (node (ref "U14") (pin "24") (pinfunction "OA1_24") (pintype "passive"))
    )
    (net (code "145") (name "Net-(U14-OA2)") (class "Default")
      (node (ref "P18") (pin "1") (pinfunction "1_1") (pintype "passive"))
      (node (ref "U14") (pin "21") (pinfunction "OA2_21") (pintype "passive"))
    )
    (net (code "146") (name "Net-(U14-OB1)") (class "Default")
      (node (ref "P18") (pin "3") (pinfunction "3_3") (pintype "passive"))
      (node (ref "U14") (pin "26") (pinfunction "OB1_26") (pintype "passive"))
    )
    (net (code "147") (name "Net-(U14-OB2)") (class "Default")
      (node (ref "P18") (pin "4") (pinfunction "4_4") (pintype "passive"))
      (node (ref "U14") (pin "1") (pinfunction "OB2_1") (pintype "passive"))
    )
    (net (code "148") (name "Net-(U14-PDN_UART)") (class "Default")
      (node (ref "RP8") (pin "5") (pinfunction "1_5") (pintype "passive"))
      (node (ref "U14") (pin "14") (pinfunction "PDN_UART_14") (pintype "passive"))
    )
    (net (code "149") (name "Net-(U14-VCP)") (class "Default")
      (node (ref "C55") (pin "1") (pinfunction "1_1") (pintype "passive"))
      (node (ref "U14") (pin "6") (pinfunction "VCP_6") (pintype "passive"))
    )
    (net (code "150") (name "Net-(U14-VREF)") (class "Default")
      (node (ref "U14") (pin "17") (pinfunction "VREF_17") (pintype "passive"))
      (node (ref "VR4") (pin "2") (pinfunction "2_2") (pintype "passive"))
    )
    (net (code "151") (name "Net-(U15-5VOUT)") (class "Default")
      (node (ref "C61") (pin "1") (pinfunction "1_1") (pintype "passive"))
      (node (ref "U15") (pin "8") (pinfunction "5VOUT_8") (pintype "passive"))
    )
    (net (code "152") (name "Net-(U15-BRA)") (class "Default")
      (node (ref "R39") (pin "1") (pinfunction "1_1") (pintype "passive"))
      (node (ref "U15") (pin "23") (pinfunction "BRA_23") (pintype "passive"))
    )
    (net (code "153") (name "Net-(U15-BRB)") (class "Default")
      (node (ref "R44") (pin "1") (pinfunction "1_1") (pintype "passive"))
      (node (ref "U15") (pin "27") (pinfunction "BRB_27") (pintype "passive"))
    )
    (net (code "154") (name "Net-(U15-CLK)") (class "Default")
      (node (ref "RP9") (pin "6") (pinfunction "1_6") (pintype "passive"))
      (node (ref "U15") (pin "13") (pinfunction "CLK_13") (pintype "passive"))
    )
    (net (code "155") (name "Net-(U15-CPI)") (class "Default")
      (node (ref "C36") (pin "2") (pinfunction "2_2") (pintype "passive"))
      (node (ref "U15") (pin "5") (pinfunction "CPI_5") (pintype "passive"))
    )
    (net (code "156") (name "Net-(U15-CPO)") (class "Default")
      (node (ref "C36") (pin "1") (pinfunction "1_1") (pintype "passive"))
      (node (ref "U15") (pin "4") (pinfunction "CPO_4") (pintype "passive"))
    )
    (net (code "157") (name "Net-(U15-DIAG)") (class "Default")
      (node (ref "RP9") (pin "8") (pinfunction "1_8") (pintype "passive"))
      (node (ref "U15") (pin "11") (pinfunction "DIAG_11") (pintype "passive"))
    )
    (net (code "158") (name "Net-(U15-INDEX)") (class "Default")
      (node (ref "RP9") (pin "7") (pinfunction "1_7") (pintype "passive"))
      (node (ref "U15") (pin "12") (pinfunction "INDEX_12") (pintype "passive"))
    )
    (net (code "159") (name "Net-(U15-OA1)") (class "Default")
      (node (ref "P19") (pin "2") (pinfunction "2_2") (pintype "passive"))
      (node (ref "U15") (pin "24") (pinfunction "OA1_24") (pintype "passive"))
    )
    (net (code "160") (name "Net-(U15-OA2)") (class "Default")
      (node (ref "P19") (pin "1") (pinfunction "1_1") (pintype "passive"))
      (node (ref "U15") (pin "21") (pinfunction "OA2_21") (pintype "passive"))
    )
    (net (code "161") (name "Net-(U15-OB1)") (class "Default")
      (node (ref "P19") (pin "3") (pinfunction "3_3") (pintype "passive"))
      (node (ref "U15") (pin "26") (pinfunction "OB1_26") (pintype "passive"))
    )
    (net (code "162") (name "Net-(U15-OB2)") (class "Default")
      (node (ref "P19") (pin "4") (pinfunction "4_4") (pintype "passive"))
      (node (ref "U15") (pin "1") (pinfunction "OB2_1") (pintype "passive"))
    )
    (net (code "163") (name "Net-(U15-PDN_UART)") (class "Default")
      (node (ref "RP9") (pin "5") (pinfunction "1_5") (pintype "passive"))
      (node (ref "U15") (pin "14") (pinfunction "PDN_UART_14") (pintype "passive"))
    )
    (net (code "164") (name "Net-(U15-VCP)") (class "Default")
      (node (ref "C56") (pin "1") (pinfunction "1_1") (pintype "passive"))
      (node (ref "U15") (pin "6") (pinfunction "VCP_6") (pintype "passive"))
    )
    (net (code "165") (name "Net-(U15-VREF)") (class "Default")
      (node (ref "U15") (pin "17") (pinfunction "VREF_17") (pintype "passive"))
      (node (ref "VR5") (pin "2") (pinfunction "2_2") (pintype "passive"))
    )
    (net (code "166") (name "VCC") (class "Default")
      (node (ref "C37") (pin "1") (pinfunction "1_1") (pintype "passive"))
      (node (ref "C38") (pin "1") (pinfunction "1_1") (pintype "passive"))
      (node (ref "C39") (pin "1") (pinfunction "1_1") (pintype "passive"))
      (node (ref "C40") (pin "1") (pinfunction "1_1") (pintype "passive"))
      (node (ref "C41") (pin "1") (pinfunction "1_1") (pintype "passive"))
      (node (ref "C42") (pin "1") (pinfunction "1_1") (pintype "passive"))
      (node (ref "C43") (pin "1") (pinfunction "1_1") (pintype "passive"))
      (node (ref "C44") (pin "1") (pinfunction "1_1") (pintype "passive"))
      (node (ref "C45") (pin "1") (pinfunction "1_1") (pintype "passive"))
      (node (ref "C46") (pin "1") (pinfunction "1_1") (pintype "passive"))
      (node (ref "C47") (pin "1") (pinfunction "1_1") (pintype "passive"))
      (node (ref "C48") (pin "1") (pinfunction "1_1") (pintype "passive"))
      (node (ref "C49") (pin "1") (pinfunction "1_1") (pintype "passive"))
      (node (ref "C50") (pin "1") (pinfunction "1_1") (pintype "passive"))
      (node (ref "C51") (pin "1") (pinfunction "1_1") (pintype "passive"))
      (node (ref "C52") (pin "2") (pinfunction "2_2") (pintype "passive"))
      (node (ref "C53") (pin "2") (pinfunction "2_2") (pintype "passive"))
      (node (ref "C54") (pin "2") (pinfunction "2_2") (pintype "passive"))
      (node (ref "C55") (pin "2") (pinfunction "2_2") (pintype "passive"))
      (node (ref "C56") (pin "2") (pinfunction "2_2") (pintype "passive"))
      (node (ref "F1") (pin "2") (pinfunction "2_2") (pintype "passive"))
      (node (ref "U11") (pin "22") (pinfunction "VS_22") (pintype "passive"))
      (node (ref "U11") (pin "28") (pinfunction "VS_28") (pintype "passive"))
      (node (ref "U12") (pin "22") (pinfunction "VS_22") (pintype "passive"))
      (node (ref "U12") (pin "28") (pinfunction "VS_28") (pintype "passive"))
      (node (ref "U13") (pin "22") (pinfunction "VS_22") (pintype "passive"))
      (node (ref "U13") (pin "28") (pinfunction "VS_28") (pintype "passive"))
      (node (ref "U14") (pin "22") (pinfunction "VS_22") (pintype "passive"))
      (node (ref "U14") (pin "28") (pinfunction "VS_28") (pintype "passive"))
      (node (ref "U15") (pin "22") (pinfunction "VS_22") (pintype "passive"))
      (node (ref "U15") (pin "28") (pinfunction "VS_28") (pintype "passive"))
    )
    (net (code "167") (name "VCC_FAN") (class "Default")
      (node (ref "F3") (pin "2") (pinfunction "2_2") (pintype "passive"))
      (node (ref "P10") (pin "2") (pinfunction "2_2") (pintype "passive"))
      (node (ref "P13") (pin "2") (pinfunction "2_2") (pintype "passive"))
      (node (ref "P14") (pin "2") (pinfunction "2_2") (pintype "passive"))
    )
    (net (code "168") (name "VCC_HEATER") (class "Default")
      (node (ref "D3") (pin "2") (pinfunction "K_2") (pintype "passive"))
      (node (ref "D4") (pin "2") (pinfunction "K_2") (pintype "passive"))
      (node (ref "F2") (pin "2") (pinfunction "2_2") (pintype "passive"))
      (node (ref "P11") (pin "1") (pinfunction "1_1") (pintype "passive"))
      (node (ref "P12") (pin "1") (pinfunction "1_1") (pintype "passive"))
      (node (ref "R20") (pin "2") (pinfunction "2_2") (pintype "passive"))
      (node (ref "R21") (pin "2") (pinfunction "2_2") (pintype "passive"))
    )
    (net (code "169") (name "VIN") (class "Default")
      (node (ref "C22") (pin "1") (pinfunction "1_1") (pintype "passive"))
      (node (ref "C23") (pin "1") (pinfunction "1_1") (pintype "passive"))
      (node (ref "F1") (pin "1") (pinfunction "1_1") (pintype "passive"))
      (node (ref "F2") (pin "1") (pinfunction "1_1") (pintype "passive"))
      (node (ref "F3") (pin "1") (pinfunction "1_1") (pintype "passive"))
      (node (ref "P9") (pin "1") (pinfunction "1_1") (pintype "passive"))
      (node (ref "R12") (pin "1") (pinfunction "1_1") (pintype "passive"))
      (node (ref "U7") (pin "2") (pinfunction "IN_2") (pintype "passive"))
    )
    (net (code "170") (name "unconnected-(P1-ID-Pad4)") (class "Default")
      (node (ref "P1") (pin "4") (pinfunction "ID_4") (pintype "passive+no_connect"))
    )
    (net (code "171") (name "unconnected-(P1-SHIELD-Pad6)") (class "Default")
      (node (ref "P1") (pin "6") (pinfunction "SHIELD_6") (pintype "passive+no_connect"))
    )
    (net (code "172") (name "unconnected-(P2-Pad2)") (class "Default")
      (node (ref "P2") (pin "2") (pinfunction "2_2") (pintype "passive+no_connect"))
    )
    (net (code "173") (name "unconnected-(P2-Pad5)") (class "Default")
      (node (ref "P2") (pin "5") (pinfunction "5_5") (pintype "passive+no_connect"))
    )
    (net (code "174") (name "unconnected-(RP1-Pad1)") (class "Default")
      (node (ref "RP1") (pin "1") (pinfunction "1_1") (pintype "passive"))
    )
    (net (code "175") (name "unconnected-(RP2-1-Pad4)") (class "Default")
      (node (ref "RP2") (pin "4") (pinfunction "1_4") (pintype "passive"))
    )
    (net (code "176") (name "unconnected-(RP2-1-Pad5)") (class "Default")
      (node (ref "RP2") (pin "5") (pinfunction "1_5") (pintype "passive"))
    )
    (net (code "177") (name "unconnected-(RP3-Pad1)") (class "Default")
      (node (ref "RP3") (pin "1") (pinfunction "1_1") (pintype "passive+no_connect"))
    )
    (net (code "178") (name "unconnected-(U1-PA0-WKUP{slash}USART2_CTS{slash}ADC123_IN0{slash}TIM5_CH1{slash}TIM2_CH1_ETR{slash}TIM8_ETR-Pad14)") (class "Default")
      (node (ref "U1") (pin "14") (pinfunction "PA0-WKUP/USART2_CTS/ADC123_IN0/TIM5_CH1/TIM2_CH1_ETR/TIM8_ETR_14") (pintype "passive"))
    )
    (net (code "179") (name "unconnected-(U1-PA1{slash}USART2_RTS{slash}ADC123_IN1{slash}TIM5_CH2{slash}TIM2_CH2-Pad15)") (class "Default")
      (node (ref "U1") (pin "15") (pinfunction "PA1/USART2_RTS/ADC123_IN1/TIM5_CH2/TIM2_CH2_15") (pintype "passive"))
    )
    (net (code "180") (name "unconnected-(U1-PB0{slash}ADC12_IN8{slash}TIM3_CH3{slash}TIM8_CH2N-Pad26)") (class "Default")
      (node (ref "U1") (pin "26") (pinfunction "PB0/ADC12_IN8/TIM3_CH3/TIM8_CH2N_26") (pintype "passive"))
    )
    (net (code "181") (name "unconnected-(U1-PB9{slash}TIM4_CH4{slash}SDIO_D5-Pad62)") (class "Default")
      (node (ref "U1") (pin "62") (pinfunction "PB9/TIM4_CH4/SDIO_D5_62") (pintype "passive"))
    )
    (net (code "182") (name "unconnected-(U1-PC0{slash}ADC123_IN10-Pad8)") (class "Default")
      (node (ref "U1") (pin "8") (pinfunction "PC0/ADC123_IN10_8") (pintype "passive"))
    )
    (net (code "183") (name "unconnected-(U1-PC1{slash}ADC123_IN11-Pad9)") (class "Default")
      (node (ref "U1") (pin "9") (pinfunction "PC1/ADC123_IN11_9") (pintype "passive"))
    )
    (net (code "184") (name "unconnected-(U1-PC13{slash}TAMPER-RTC-Pad2)") (class "Default")
      (node (ref "U1") (pin "2") (pinfunction "PC13/TAMPER-RTC_2") (pintype "passive"))
    )
    (net (code "185") (name "unconnected-(U1-PC14{slash}OSC32_IN-Pad3)") (class "Default")
      (node (ref "U1") (pin "3") (pinfunction "PC14/OSC32_IN_3") (pintype "passive"))
    )
    (net (code "186") (name "unconnected-(U1-PC15{slash}OSC32_OUT-Pad4)") (class "Default")
      (node (ref "U1") (pin "4") (pinfunction "PC15/OSC32_OUT_4") (pintype "passive"))
    )
    (net (code "187") (name "unconnected-(U1-VBAT-Pad1)") (class "Default")
      (node (ref "U1") (pin "1") (pinfunction "VBAT_1") (pintype "passive+no_connect"))
    )
    (net (code "188") (name "unconnected-(U2-A3-Pad5)") (class "Default")
      (node (ref "U2") (pin "5") (pinfunction "A3_5") (pintype "passive"))
    )
    (net (code "189") (name "unconnected-(U2-A4-Pad6)") (class "Default")
      (node (ref "U2") (pin "6") (pinfunction "A4_6") (pintype "passive"))
    )
    (net (code "190") (name "unconnected-(U2-A5-Pad7)") (class "Default")
      (node (ref "U2") (pin "7") (pinfunction "A5_7") (pintype "passive"))
    )
    (net (code "191") (name "unconnected-(U2-A6-Pad8)") (class "Default")
      (node (ref "U2") (pin "8") (pinfunction "A6_8") (pintype "passive"))
    )
    (net (code "192") (name "unconnected-(U2-A7-Pad9)") (class "Default")
      (node (ref "U2") (pin "9") (pinfunction "A7_9") (pintype "passive"))
    )
    (net (code "193") (name "unconnected-(U2-B3-Pad15)") (class "Default")
      (node (ref "U2") (pin "15") (pinfunction "B3_15") (pintype "passive"))
    )
    (net (code "194") (name "unconnected-(U2-B4-Pad14)") (class "Default")
      (node (ref "U2") (pin "14") (pinfunction "B4_14") (pintype "passive"))
    )
    (net (code "195") (name "unconnected-(U2-B5-Pad13)") (class "Default")
      (node (ref "U2") (pin "13") (pinfunction "B5_13") (pintype "passive"))
    )
    (net (code "196") (name "unconnected-(U2-B6-Pad12)") (class "Default")
      (node (ref "U2") (pin "12") (pinfunction "B6_12") (pintype "passive"))
    )
    (net (code "197") (name "unconnected-(U2-B7-Pad11)") (class "Default")
      (node (ref "U2") (pin "11") (pinfunction "B7_11") (pintype "passive"))
    )
    (net (code "198") (name "unconnected-(U3-R232-Pad15)") (class "Default")
      (node (ref "U3") (pin "15") (pinfunction "R232_15") (pintype "passive+no_connect"))
    )
    (net (code "199") (name "unconnected-(U3-~{CTS}-Pad9)") (class "Default")
      (node (ref "U3") (pin "9") (pinfunction "~{CTS}_9") (pintype "passive+no_connect"))
    )
    (net (code "200") (name "unconnected-(U3-~{DCD}-Pad12)") (class "Default")
      (node (ref "U3") (pin "12") (pinfunction "~{DCD}_12") (pintype "passive+no_connect"))
    )
    (net (code "201") (name "unconnected-(U3-~{DSR}-Pad10)") (class "Default")
      (node (ref "U3") (pin "10") (pinfunction "~{DSR}_10") (pintype "passive+no_connect"))
    )
    (net (code "202") (name "unconnected-(U3-~{DTR}-Pad13)") (class "Default")
      (node (ref "U3") (pin "13") (pinfunction "~{DTR}_13") (pintype "passive+no_connect"))
    )
    (net (code "203") (name "unconnected-(U3-~{RI}-Pad11)") (class "Default")
      (node (ref "U3") (pin "11") (pinfunction "~{RI}_11") (pintype "passive+no_connect"))
    )
    (net (code "204") (name "unconnected-(U3-~{RTS}-Pad14)") (class "Default")
      (node (ref "U3") (pin "14") (pinfunction "~{RTS}_14") (pintype "passive+no_connect"))
    )
    (net (code "205") (name "unconnected-(U5-PA0-Pad3)") (class "Default")
      (node (ref "U5") (pin "3") (pinfunction "PA0_3") (pintype "passive+no_connect"))
    )
    (net (code "206") (name "unconnected-(U5-PA3-Pad4)") (class "Default")
      (node (ref "U5") (pin "4") (pinfunction "PA3_4") (pintype "passive+no_connect"))
    )
    (net (code "207") (name "unconnected-(U6-SD-Pad1)") (class "Default")
      (node (ref "U6") (pin "1") (pinfunction "SD_1") (pintype "passive+no_connect"))
    )
    (net (code "208") (name "unconnected-(U9-D2-Pad4)") (class "Default")
      (node (ref "U9") (pin "4") (pinfunction "D2_4") (pintype "passive"))
    )
    (net (code "209") (name "unconnected-(U9-G2-Pad3)") (class "Default")
      (node (ref "U9") (pin "3") (pinfunction "G2_3") (pintype "passive"))
    )
  )
)
